# EmphaseMainBoard.net
KiCad netlist of a schematic drawn in Altium Designer
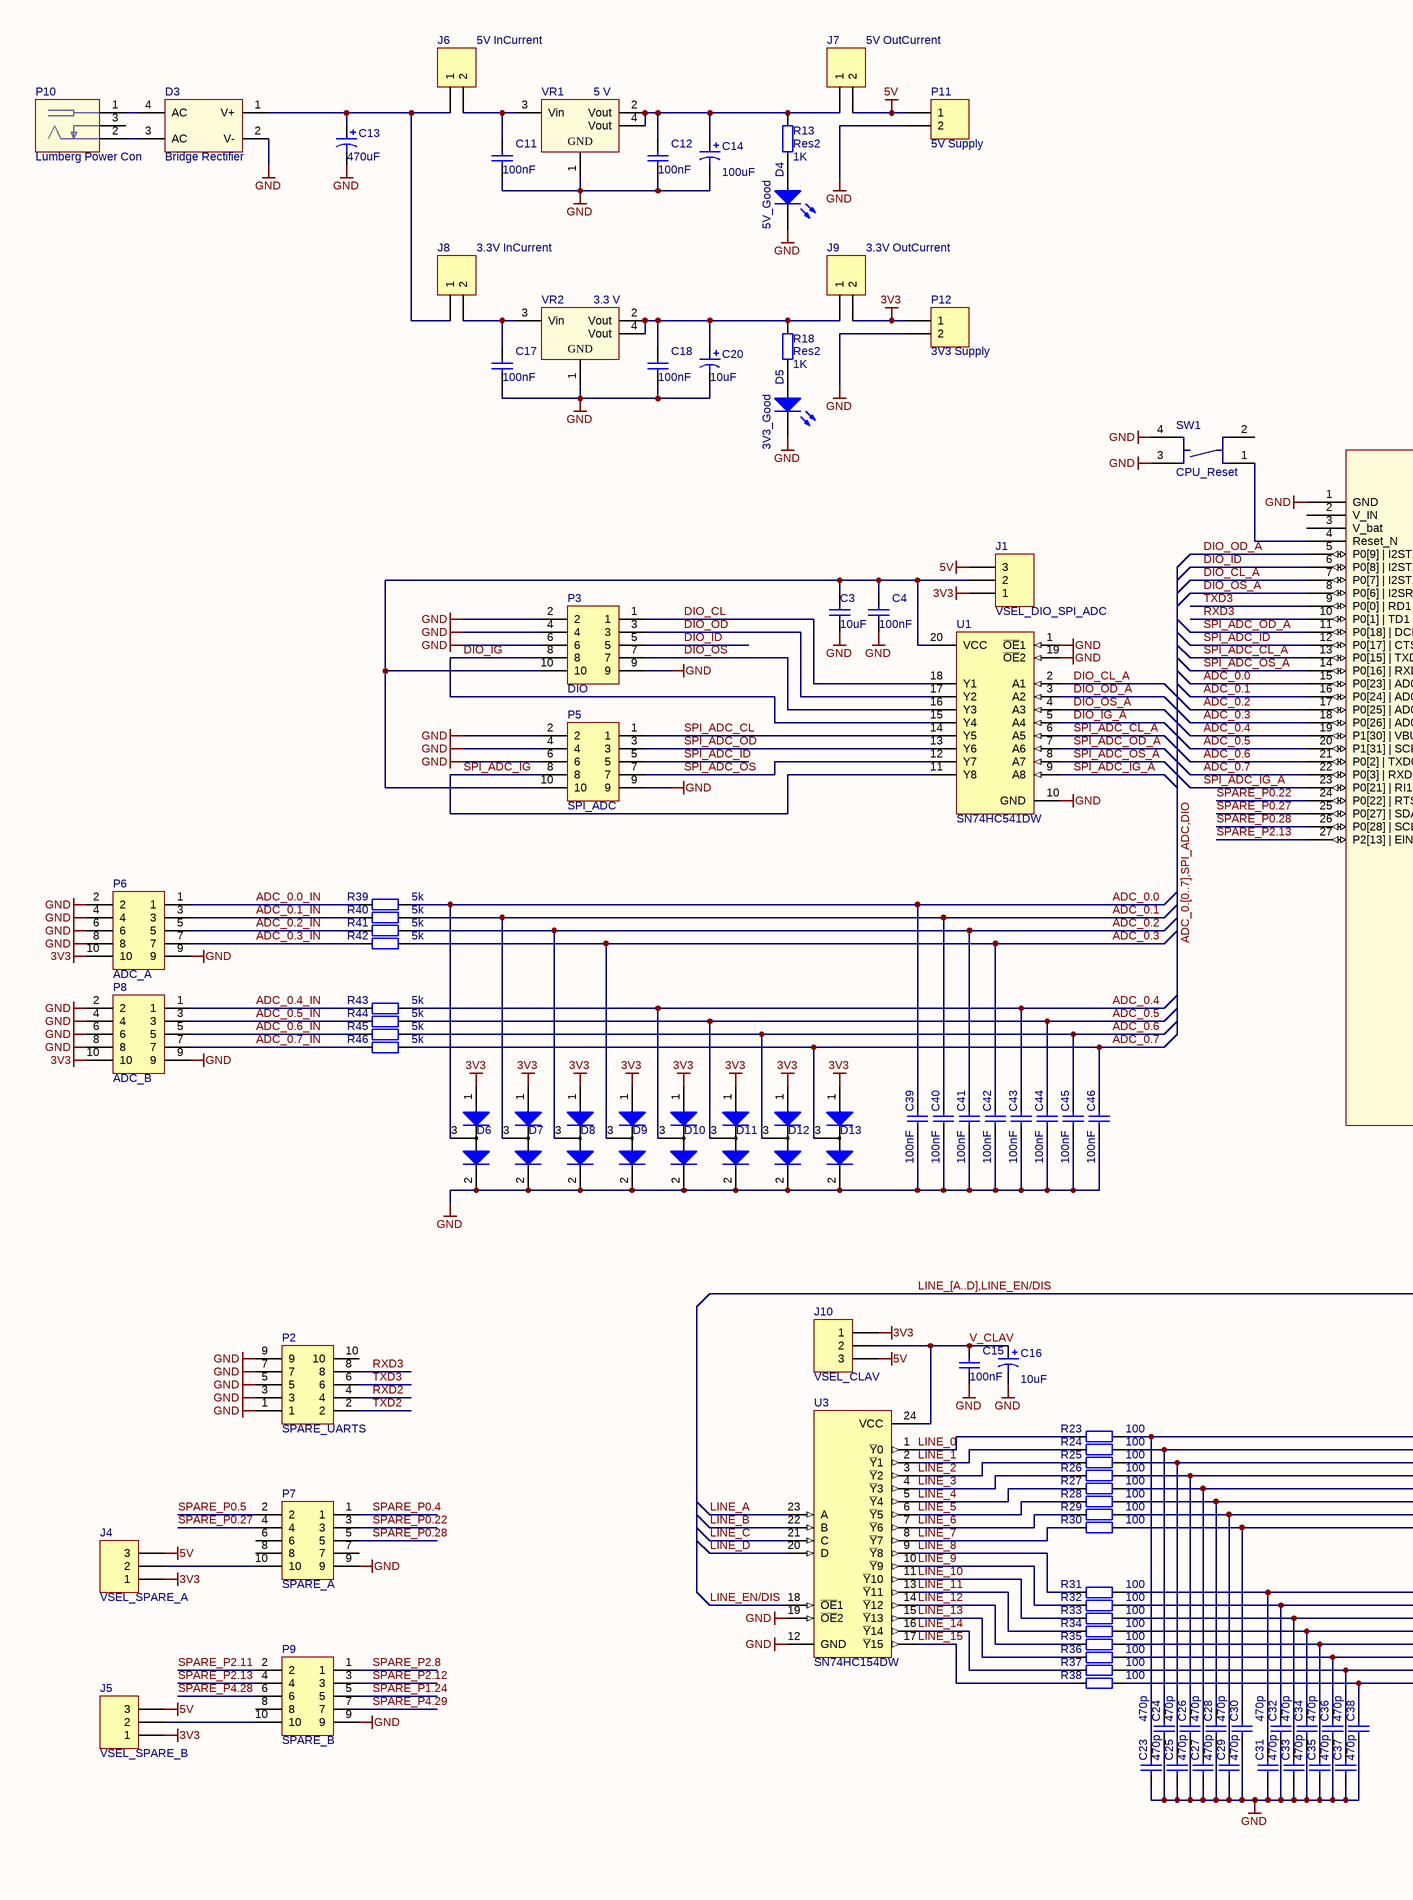
[diagram p0: EmphaseMainBoard.SchDoc, left]
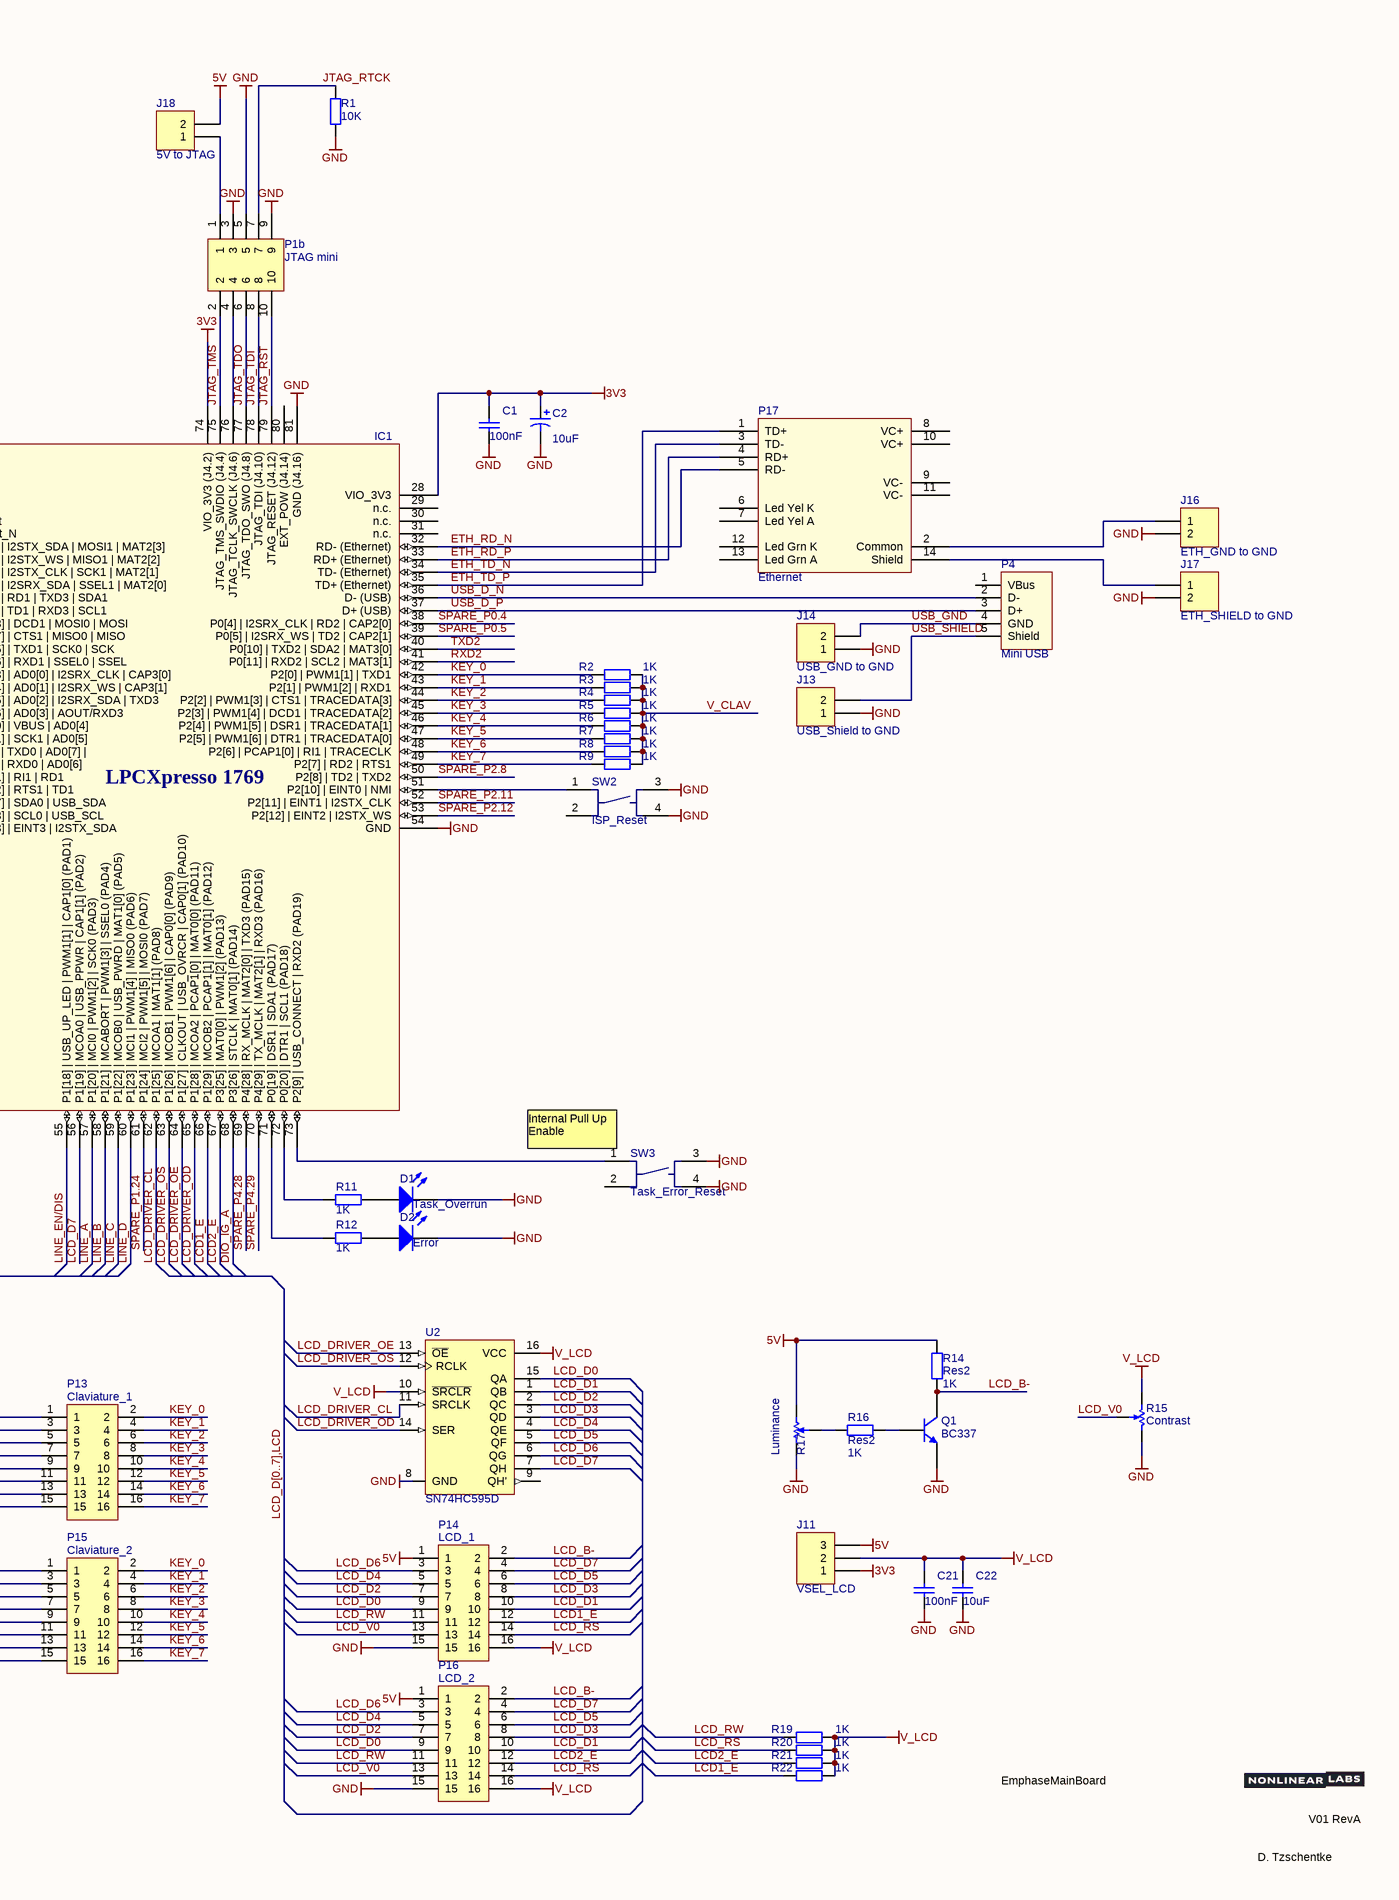
[diagram p1: EmphaseMainBoard.SchDoc, right]

(export (version "E")
  (design (tool "Eeschema 10.0.6"))
  (components
    (comp (ref "C1")
      (value "100nF")
      (footprint "6-0805_N")
      (description "Capacitor (Semiconductor SIM Model)")
      (fields (field (name "Comment") "Cap Semi") (field (name "PUBLISHER") "Altium Limited"))
      (libsource (lib "Miscellaneous Devices") (part "Cap Semi"))
    )
    (comp (ref "C2")
      (value "10uF")
      (footprint "6-0805_N")
      (description "Polarized Capacitor (Radial)")
      (fields (field (name "Comment") "Cap Pol1") (field (name "PUBLISHER") "Altium Limited"))
      (libsource (lib "Miscellaneous Devices") (part "Cap Pol1"))
    )
    (comp (ref "C3")
      (value "10uF")
      (footprint "6-0805_N")
      (description "Capacitor (Semiconductor SIM Model)")
      (fields (field (name "Comment") "Cap Semi") (field (name "PUBLISHER") "Altium Limited"))
      (libsource (lib "Miscellaneous Devices") (part "Cap Semi"))
    )
    (comp (ref "C4")
      (value "100nF")
      (footprint "6-0805_N")
      (description "Capacitor (Semiconductor SIM Model)")
      (fields (field (name "Comment") "Cap Semi") (field (name "PUBLISHER") "Altium Limited"))
      (libsource (lib "Miscellaneous Devices") (part "Cap Semi"))
    )
    (comp (ref "C11")
      (value "100nF")
      (footprint "6-0805_N")
      (description "Capacitor (Semiconductor SIM Model)")
      (fields (field (name "Comment") "Cap Semi") (field (name "PUBLISHER") "Altium Limited"))
      (libsource (lib "Miscellaneous Devices") (part "Cap Semi"))
    )
    (comp (ref "C12")
      (value "100nF")
      (footprint "6-0805_N")
      (description "Capacitor (Semiconductor SIM Model)")
      (fields (field (name "Comment") "Cap Semi") (field (name "PUBLISHER") "Altium Limited"))
      (libsource (lib "Miscellaneous Devices") (part "Cap Semi"))
    )
    (comp (ref "C13")
      (value "470uF")
      (footprint "CAPPR3.5-8x20")
      (description "Polarized Capacitor (Radial)")
      (fields (field (name "Comment") "Cap Pol1") (field (name "PUBLISHER") "Altium Limited"))
      (libsource (lib "Miscellaneous Devices") (part "Cap Pol1"))
    )
    (comp (ref "C14")
      (value "100uF")
      (footprint "CAPPR2.5-6.3x11")
      (description "Polarized Capacitor (Radial)")
      (fields (field (name "Comment") "Cap Pol1") (field (name "PUBLISHER") "Altium Limited"))
      (libsource (lib "Miscellaneous Devices") (part "Cap Pol1"))
    )
    (comp (ref "C15")
      (value "100nF")
      (footprint "6-0805_N")
      (description "Capacitor (Semiconductor SIM Model)")
      (fields (field (name "Comment") "Cap Semi") (field (name "PUBLISHER") "Altium Limited"))
      (libsource (lib "Miscellaneous Devices") (part "Cap Semi"))
    )
    (comp (ref "C16")
      (value "10uF")
      (footprint "6-0805_N")
      (description "Polarized Capacitor (Radial)")
      (fields (field (name "Comment") "Cap Pol1") (field (name "PUBLISHER") "Altium Limited"))
      (libsource (lib "Miscellaneous Devices") (part "Cap Pol1"))
    )
    (comp (ref "C17")
      (value "100nF")
      (footprint "6-0805_N")
      (description "Capacitor (Semiconductor SIM Model)")
      (fields (field (name "Comment") "Cap Semi") (field (name "PUBLISHER") "Altium Limited"))
      (libsource (lib "Miscellaneous Devices") (part "Cap Semi"))
    )
    (comp (ref "C18")
      (value "100nF")
      (footprint "6-0805_N")
      (description "Capacitor (Semiconductor SIM Model)")
      (fields (field (name "Comment") "Cap Semi") (field (name "PUBLISHER") "Altium Limited"))
      (libsource (lib "Miscellaneous Devices") (part "Cap Semi"))
    )
    (comp (ref "C20")
      (value "10uF")
      (footprint "CAPPR2.5-6.3x11")
      (description "Polarized Capacitor (Radial)")
      (fields (field (name "Comment") "Cap Pol1") (field (name "PUBLISHER") "Altium Limited"))
      (libsource (lib "Miscellaneous Devices") (part "Cap Pol1"))
    )
    (comp (ref "C21")
      (value "100nF")
      (footprint "6-0805_N")
      (description "Capacitor (Semiconductor SIM Model)")
      (fields (field (name "Comment") "Cap Semi") (field (name "PUBLISHER") "Altium Limited"))
      (libsource (lib "Miscellaneous Devices") (part "Cap Semi"))
    )
    (comp (ref "C22")
      (value "10uF")
      (footprint "6-0805_N")
      (description "Capacitor (Semiconductor SIM Model)")
      (fields (field (name "Comment") "Cap Semi") (field (name "PUBLISHER") "Altium Limited"))
      (libsource (lib "Miscellaneous Devices") (part "Cap Semi"))
    )
    (comp (ref "C23")
      (value "470p")
      (footprint "6-0805_N")
      (description "Capacitor (Semiconductor SIM Model)")
      (fields (field (name "Comment") "Cap Semi") (field (name "PUBLISHER") "Altium Limited"))
      (libsource (lib "Miscellaneous Devices") (part "Cap Semi"))
    )
    (comp (ref "C24")
      (value "470p")
      (footprint "6-0805_N")
      (description "Capacitor (Semiconductor SIM Model)")
      (fields (field (name "Comment") "Cap Semi") (field (name "PUBLISHER") "Altium Limited"))
      (libsource (lib "Miscellaneous Devices") (part "Cap Semi"))
    )
    (comp (ref "C25")
      (value "470p")
      (footprint "6-0805_N")
      (description "Capacitor (Semiconductor SIM Model)")
      (fields (field (name "Comment") "Cap Semi") (field (name "PUBLISHER") "Altium Limited"))
      (libsource (lib "Miscellaneous Devices") (part "Cap Semi"))
    )
    (comp (ref "C26")
      (value "470p")
      (footprint "6-0805_N")
      (description "Capacitor (Semiconductor SIM Model)")
      (fields (field (name "Comment") "Cap Semi") (field (name "PUBLISHER") "Altium Limited"))
      (libsource (lib "Miscellaneous Devices") (part "Cap Semi"))
    )
    (comp (ref "C27")
      (value "470p")
      (footprint "6-0805_N")
      (description "Capacitor (Semiconductor SIM Model)")
      (fields (field (name "Comment") "Cap Semi") (field (name "PUBLISHER") "Altium Limited"))
      (libsource (lib "Miscellaneous Devices") (part "Cap Semi"))
    )
    (comp (ref "C28")
      (value "470p")
      (footprint "6-0805_N")
      (description "Capacitor (Semiconductor SIM Model)")
      (fields (field (name "Comment") "Cap Semi") (field (name "PUBLISHER") "Altium Limited"))
      (libsource (lib "Miscellaneous Devices") (part "Cap Semi"))
    )
    (comp (ref "C29")
      (value "470p")
      (footprint "6-0805_N")
      (description "Capacitor (Semiconductor SIM Model)")
      (fields (field (name "Comment") "Cap Semi") (field (name "PUBLISHER") "Altium Limited"))
      (libsource (lib "Miscellaneous Devices") (part "Cap Semi"))
    )
    (comp (ref "C30")
      (value "470p")
      (footprint "6-0805_N")
      (description "Capacitor (Semiconductor SIM Model)")
      (fields (field (name "Comment") "Cap Semi") (field (name "PUBLISHER") "Altium Limited"))
      (libsource (lib "Miscellaneous Devices") (part "Cap Semi"))
    )
    (comp (ref "C31")
      (value "470p")
      (footprint "6-0805_N")
      (description "Capacitor (Semiconductor SIM Model)")
      (fields (field (name "Comment") "Cap Semi") (field (name "PUBLISHER") "Altium Limited"))
      (libsource (lib "Miscellaneous Devices") (part "Cap Semi"))
    )
    (comp (ref "C32")
      (value "470p")
      (footprint "6-0805_N")
      (description "Capacitor (Semiconductor SIM Model)")
      (fields (field (name "Comment") "Cap Semi") (field (name "PUBLISHER") "Altium Limited"))
      (libsource (lib "Miscellaneous Devices") (part "Cap Semi"))
    )
    (comp (ref "C33")
      (value "470p")
      (footprint "6-0805_N")
      (description "Capacitor (Semiconductor SIM Model)")
      (fields (field (name "Comment") "Cap Semi") (field (name "PUBLISHER") "Altium Limited"))
      (libsource (lib "Miscellaneous Devices") (part "Cap Semi"))
    )
    (comp (ref "C34")
      (value "470p")
      (footprint "6-0805_N")
      (description "Capacitor (Semiconductor SIM Model)")
      (fields (field (name "Comment") "Cap Semi") (field (name "PUBLISHER") "Altium Limited"))
      (libsource (lib "Miscellaneous Devices") (part "Cap Semi"))
    )
    (comp (ref "C35")
      (value "470p")
      (footprint "6-0805_N")
      (description "Capacitor (Semiconductor SIM Model)")
      (fields (field (name "Comment") "Cap Semi") (field (name "PUBLISHER") "Altium Limited"))
      (libsource (lib "Miscellaneous Devices") (part "Cap Semi"))
    )
    (comp (ref "C36")
      (value "470p")
      (footprint "6-0805_N")
      (description "Capacitor (Semiconductor SIM Model)")
      (fields (field (name "Comment") "Cap Semi") (field (name "PUBLISHER") "Altium Limited"))
      (libsource (lib "Miscellaneous Devices") (part "Cap Semi"))
    )
    (comp (ref "C37")
      (value "470p")
      (footprint "6-0805_N")
      (description "Capacitor (Semiconductor SIM Model)")
      (fields (field (name "Comment") "Cap Semi") (field (name "PUBLISHER") "Altium Limited"))
      (libsource (lib "Miscellaneous Devices") (part "Cap Semi"))
    )
    (comp (ref "C38")
      (value "470p")
      (footprint "6-0805_N")
      (description "Capacitor (Semiconductor SIM Model)")
      (fields (field (name "Comment") "Cap Semi") (field (name "PUBLISHER") "Altium Limited"))
      (libsource (lib "Miscellaneous Devices") (part "Cap Semi"))
    )
    (comp (ref "C39")
      (value "100nF")
      (footprint "6-0805_N")
      (description "Capacitor (Semiconductor SIM Model)")
      (fields (field (name "Comment") "Cap Semi") (field (name "PUBLISHER") "Altium Limited"))
      (libsource (lib "Miscellaneous Devices") (part "Cap Semi"))
    )
    (comp (ref "C40")
      (value "100nF")
      (footprint "6-0805_N")
      (description "Capacitor (Semiconductor SIM Model)")
      (fields (field (name "Comment") "Cap Semi") (field (name "PUBLISHER") "Altium Limited"))
      (libsource (lib "Miscellaneous Devices") (part "Cap Semi"))
    )
    (comp (ref "C41")
      (value "100nF")
      (footprint "6-0805_N")
      (description "Capacitor (Semiconductor SIM Model)")
      (fields (field (name "Comment") "Cap Semi") (field (name "PUBLISHER") "Altium Limited"))
      (libsource (lib "Miscellaneous Devices") (part "Cap Semi"))
    )
    (comp (ref "C42")
      (value "100nF")
      (footprint "6-0805_N")
      (description "Capacitor (Semiconductor SIM Model)")
      (fields (field (name "Comment") "Cap Semi") (field (name "PUBLISHER") "Altium Limited"))
      (libsource (lib "Miscellaneous Devices") (part "Cap Semi"))
    )
    (comp (ref "C43")
      (value "100nF")
      (footprint "6-0805_N")
      (description "Capacitor (Semiconductor SIM Model)")
      (fields (field (name "Comment") "Cap Semi") (field (name "PUBLISHER") "Altium Limited"))
      (libsource (lib "Miscellaneous Devices") (part "Cap Semi"))
    )
    (comp (ref "C44")
      (value "100nF")
      (footprint "6-0805_N")
      (description "Capacitor (Semiconductor SIM Model)")
      (fields (field (name "Comment") "Cap Semi") (field (name "PUBLISHER") "Altium Limited"))
      (libsource (lib "Miscellaneous Devices") (part "Cap Semi"))
    )
    (comp (ref "C45")
      (value "100nF")
      (footprint "6-0805_N")
      (description "Capacitor (Semiconductor SIM Model)")
      (fields (field (name "Comment") "Cap Semi") (field (name "PUBLISHER") "Altium Limited"))
      (libsource (lib "Miscellaneous Devices") (part "Cap Semi"))
    )
    (comp (ref "C46")
      (value "100nF")
      (footprint "6-0805_N")
      (description "Capacitor (Semiconductor SIM Model)")
      (fields (field (name "Comment") "Cap Semi") (field (name "PUBLISHER") "Altium Limited"))
      (libsource (lib "Miscellaneous Devices") (part "Cap Semi"))
    )
    (comp (ref "D1")
      (value "Task_Overrun")
      (footprint "6-0805_M")
      (description "Typical BLUE SiC LED")
      (fields (field (name "PUBLISHER") "Altium Limited"))
      (libsource (lib "Miscellaneous Devices") (part "LED3"))
    )
    (comp (ref "D2")
      (value "Error")
      (footprint "6-0805_M")
      (description "Typical BLUE SiC LED")
      (fields (field (name "PUBLISHER") "Altium Limited"))
      (libsource (lib "Miscellaneous Devices") (part "LED3"))
    )
    (comp (ref "D3")
      (value "Bridge Rectifier")
      (footprint "SDIP")
      (fields (field (name "PUBLISHER") "NONLINEAR LABS"))
      (libsource (lib "BridgeRectifier") (part "Bridge Rectifiers"))
    )
    (comp (ref "D4")
      (value "5V_Good")
      (footprint "6-0805_M")
      (description "Typical BLUE SiC LED")
      (fields (field (name "PUBLISHER") "Altium Limited"))
      (libsource (lib "Miscellaneous Devices") (part "LED3"))
    )
    (comp (ref "D5")
      (value "3V3_Good")
      (footprint "6-0805_M")
      (description "Typical BLUE SiC LED")
      (fields (field (name "PUBLISHER") "Altium Limited"))
      (libsource (lib "Miscellaneous Devices") (part "LED3"))
    )
    (comp (ref "D6")
      (value "Double Diode")
      (footprint "SOT23-3N")
      (description "High Speed Double Diode")
      (fields (field (name "PUBLISHER") "NONLINEAR LABS"))
      (libsource (lib "DoubleDiode") (part "Double Diode"))
    )
    (comp (ref "D7")
      (value "Double Diode")
      (footprint "SOT23-3N")
      (description "High Speed Double Diode")
      (fields (field (name "PUBLISHER") "NONLINEAR LABS"))
      (libsource (lib "DoubleDiode") (part "Double Diode"))
    )
    (comp (ref "D8")
      (value "Double Diode")
      (footprint "SOT23-3N")
      (description "High Speed Double Diode")
      (fields (field (name "PUBLISHER") "NONLINEAR LABS"))
      (libsource (lib "DoubleDiode") (part "Double Diode"))
    )
    (comp (ref "D9")
      (value "Double Diode")
      (footprint "SOT23-3N")
      (description "High Speed Double Diode")
      (fields (field (name "PUBLISHER") "NONLINEAR LABS"))
      (libsource (lib "DoubleDiode") (part "Double Diode"))
    )
    (comp (ref "D10")
      (value "Double Diode")
      (footprint "SOT23-3N")
      (description "High Speed Double Diode")
      (fields (field (name "PUBLISHER") "NONLINEAR LABS"))
      (libsource (lib "DoubleDiode") (part "Double Diode"))
    )
    (comp (ref "D11")
      (value "Double Diode")
      (footprint "SOT23-3N")
      (description "High Speed Double Diode")
      (fields (field (name "PUBLISHER") "NONLINEAR LABS"))
      (libsource (lib "DoubleDiode") (part "Double Diode"))
    )
    (comp (ref "D12")
      (value "Double Diode")
      (footprint "SOT23-3N")
      (description "High Speed Double Diode")
      (fields (field (name "PUBLISHER") "NONLINEAR LABS"))
      (libsource (lib "DoubleDiode") (part "Double Diode"))
    )
    (comp (ref "D13")
      (value "Double Diode")
      (footprint "SOT23-3N")
      (description "High Speed Double Diode")
      (fields (field (name "PUBLISHER") "NONLINEAR LABS"))
      (libsource (lib "DoubleDiode") (part "Double Diode"))
    )
    (comp (ref "IC1")
      (value "~")
      (footprint "LPCXpresso1769")
      (description "Capacitor (Semiconductor SIM Model)")
      (libsource (lib "LPCXpresso1769") (part "Component_1"))
    )
    (comp (ref "J1")
      (value "VSEL_DIO_SPI_ADC")
      (footprint "HDR1X3")
      (description "Header, 3-Pin")
      (fields (field (name "PUBLISHER") "Altium Limited"))
      (libsource (lib "") (part "Header 3_1"))
    )
    (comp (ref "J4")
      (value "VSEL_SPARE_A")
      (footprint "HDR1X3")
      (description "Header, 3-Pin")
      (fields (field (name "PUBLISHER") "Altium Limited"))
      (libsource (lib "Miscellaneous Connectors") (part "Header 3"))
    )
    (comp (ref "J5")
      (value "VSEL_SPARE_B")
      (footprint "HDR1X3")
      (description "Header, 3-Pin")
      (fields (field (name "PUBLISHER") "Altium Limited"))
      (libsource (lib "Miscellaneous Connectors") (part "Header 3"))
    )
    (comp (ref "J6")
      (value "5V InCurrent")
      (footprint "HDR1X2")
      (description "Header, 2-Pin")
      (fields (field (name "PUBLISHER") "Altium Limited"))
      (libsource (lib "") (part "Header 2_2"))
    )
    (comp (ref "J7")
      (value "5V OutCurrent")
      (footprint "HDR1X2")
      (description "Header, 2-Pin")
      (fields (field (name "PUBLISHER") "Altium Limited"))
      (libsource (lib "") (part "Header 2_2"))
    )
    (comp (ref "J8")
      (value "3.3V InCurrent")
      (footprint "HDR1X2")
      (description "Header, 2-Pin")
      (fields (field (name "PUBLISHER") "Altium Limited"))
      (libsource (lib "") (part "Header 2_2"))
    )
    (comp (ref "J9")
      (value "3.3V OutCurrent")
      (footprint "HDR1X2")
      (description "Header, 2-Pin")
      (fields (field (name "PUBLISHER") "Altium Limited"))
      (libsource (lib "") (part "Header 2_2"))
    )
    (comp (ref "J10")
      (value "VSEL_CLAV")
      (footprint "HDR1X3")
      (description "Header, 3-Pin")
      (fields (field (name "PUBLISHER") "Altium Limited"))
      (libsource (lib "") (part "Header 3_2"))
    )
    (comp (ref "J11")
      (value "VSEL_LCD")
      (footprint "HDR1X3")
      (description "Header, 3-Pin")
      (fields (field (name "PUBLISHER") "Altium Limited"))
      (libsource (lib "Miscellaneous Connectors") (part "Header 3"))
    )
    (comp (ref "J13")
      (value "USB_Shield to GND")
      (footprint "HDR1X2")
      (description "Header, 2-Pin")
      (fields (field (name "PUBLISHER") "Altium Limited"))
      (libsource (lib "Miscellaneous Connectors") (part "Header 2"))
    )
    (comp (ref "J14")
      (value "USB_GND to GND")
      (footprint "HDR1X2")
      (description "Header, 2-Pin")
      (fields (field (name "PUBLISHER") "Altium Limited"))
      (libsource (lib "Miscellaneous Connectors") (part "Header 2"))
    )
    (comp (ref "J16")
      (value "ETH_GND to GND")
      (footprint "HDR1X2")
      (description "Header, 2-Pin")
      (fields (field (name "PUBLISHER") "Altium Limited"))
      (libsource (lib "") (part "Header 2_1"))
    )
    (comp (ref "J17")
      (value "ETH_SHIELD to GND")
      (footprint "HDR1X2")
      (description "Header, 2-Pin")
      (fields (field (name "PUBLISHER") "Altium Limited"))
      (libsource (lib "") (part "Header 2_1"))
    )
    (comp (ref "J18")
      (value "5V to JTAG")
      (footprint "HDR1X2")
      (description "Header, 2-Pin")
      (fields (field (name "PUBLISHER") "Altium Limited"))
      (libsource (lib "Miscellaneous Connectors") (part "Header 2"))
    )
    (comp (ref "P1b")
      (value "JTAG mini")
      (footprint "10 pol Header SMD")
      (description "JTAG")
      (fields (field (name "PUBLISHER") "NONLINEAR LABS"))
      (libsource (lib "") (part "10 pol Header_2"))
    )
    (comp (ref "P2")
      (value "SPARE_UARTS")
      (footprint "10 pol Header")
      (description "10 pol Header")
      (fields (field (name "PUBLISHER") "NONLINEAR LABS"))
      (libsource (lib "") (part "10 pol Header_1"))
    )
    (comp (ref "P3")
      (value "DIO")
      (footprint "10 pol Header")
      (description "10 pol Header")
      (fields (field (name "PUBLISHER") "NONLINEAR LABS"))
      (libsource (lib "10polHeader") (part "10 pol Header"))
    )
    (comp (ref "P4")
      (value "Mini USB")
      (footprint "Mini USB Socket - Typ B")
      (fields (field (name "PUBLISHER") "NONLINEAR LABS"))
      (libsource (lib "MiniUsb") (part "Mini USB Jack B"))
    )
    (comp (ref "P5")
      (value "SPI_ADC")
      (footprint "10 pol Header")
      (description "10 pol Header")
      (fields (field (name "PUBLISHER") "NONLINEAR LABS"))
      (libsource (lib "10polHeader") (part "10 pol Header"))
    )
    (comp (ref "P6")
      (value "ADC_A")
      (footprint "10 pol Header")
      (description "10 pol Header")
      (fields (field (name "PUBLISHER") "NONLINEAR LABS"))
      (libsource (lib "10polHeader") (part "10 pol Header"))
    )
    (comp (ref "P7")
      (value "SPARE_A")
      (footprint "10 pol Header")
      (description "10 pol Header")
      (fields (field (name "PUBLISHER") "NONLINEAR LABS"))
      (libsource (lib "10polHeader") (part "10 pol Header"))
    )
    (comp (ref "P8")
      (value "ADC_B")
      (footprint "10 pol Header")
      (description "10 pol Header")
      (fields (field (name "PUBLISHER") "NONLINEAR LABS"))
      (libsource (lib "10polHeader") (part "10 pol Header"))
    )
    (comp (ref "P9")
      (value "SPARE_B")
      (footprint "10 pol Header")
      (description "10 pol Header")
      (fields (field (name "PUBLISHER") "NONLINEAR LABS"))
      (libsource (lib "10polHeader") (part "10 pol Header"))
    )
    (comp (ref "P10")
      (value "Lumberg Power Con")
      (footprint "LumbergPowerCon")
      (description "Lumberg Power Connector")
      (fields (field (name "PUBLISHER") "NONLINEAR LABS"))
      (libsource (lib "LumbergPowerCon") (part "Lumberg Power Connector"))
    )
    (comp (ref "P11")
      (value "5V Supply")
      (footprint "HDR1X2")
      (description "Header, 2-Pin")
      (fields (field (name "PUBLISHER") "Altium Limited"))
      (libsource (lib "") (part "Header 2_1"))
    )
    (comp (ref "P12")
      (value "3V3 Supply")
      (footprint "HDR1X2")
      (description "Header, 2-Pin")
      (fields (field (name "PUBLISHER") "Altium Limited"))
      (libsource (lib "") (part "Header 2_1"))
    )
    (comp (ref "P13")
      (value "Claviature_1")
      (footprint "16 pol Header")
      (description "16 pol Header")
      (fields (field (name "PUBLISHER") "NONLINEAR LABS"))
      (libsource (lib "16polHeader") (part "16 pol Header"))
    )
    (comp (ref "P14")
      (value "LCD_1")
      (footprint "16 pol Header")
      (description "16 pol Header")
      (fields (field (name "PUBLISHER") "NONLINEAR LABS"))
      (libsource (lib "16polHeader") (part "16 pol Header"))
    )
    (comp (ref "P15")
      (value "Claviature_2")
      (footprint "16 pol Header")
      (description "16 pol Header")
      (fields (field (name "PUBLISHER") "NONLINEAR LABS"))
      (libsource (lib "16polHeader") (part "16 pol Header"))
    )
    (comp (ref "P16")
      (value "LCD_2")
      (footprint "16 pol Header")
      (description "16 pol Header")
      (fields (field (name "PUBLISHER") "NONLINEAR LABS"))
      (libsource (lib "16polHeader") (part "16 pol Header"))
    )
    (comp (ref "P17")
      (value "Ethernet")
      (footprint "Ethernet RJ-45")
      (description "Bel Stewart - MagJack 10/100 RJ-45 Ethernet")
      (fields (field (name "PUBLISHER") "NONLINEAR LABS"))
      (libsource (lib "BelEthernet") (part "Ethernet Jack"))
    )
    (comp (ref "Q1")
      (value "BC337")
      (footprint "TO-226-AA")
      (description "NPN Bipolar Transistor")
      (fields (field (name "PUBLISHER") "Altium Limited"))
      (libsource (lib "Miscellaneous Devices") (part "NPN"))
    )
    (comp (ref "R1")
      (value "10K")
      (footprint "6-0805")
      (description "Resistor")
      (fields (field (name "Comment") "Res2") (field (name "PUBLISHER") "Altium Limited"))
      (libsource (lib "Miscellaneous Devices") (part "Res2"))
    )
    (comp (ref "R2")
      (value "1K")
      (footprint "6-0805")
      (description "Resistor")
      (fields (field (name "Comment") "Res2") (field (name "PUBLISHER") "Altium Limited"))
      (libsource (lib "Miscellaneous Devices") (part "Res2"))
    )
    (comp (ref "R3")
      (value "1K")
      (footprint "6-0805")
      (description "Resistor")
      (fields (field (name "Comment") "Res2") (field (name "PUBLISHER") "Altium Limited"))
      (libsource (lib "Miscellaneous Devices") (part "Res2"))
    )
    (comp (ref "R4")
      (value "1K")
      (footprint "6-0805")
      (description "Resistor")
      (fields (field (name "Comment") "Res2") (field (name "PUBLISHER") "Altium Limited"))
      (libsource (lib "Miscellaneous Devices") (part "Res2"))
    )
    (comp (ref "R5")
      (value "1K")
      (footprint "6-0805")
      (description "Resistor")
      (fields (field (name "Comment") "Res2") (field (name "PUBLISHER") "Altium Limited"))
      (libsource (lib "Miscellaneous Devices") (part "Res2"))
    )
    (comp (ref "R6")
      (value "1K")
      (footprint "6-0805")
      (description "Resistor")
      (fields (field (name "Comment") "Res2") (field (name "PUBLISHER") "Altium Limited"))
      (libsource (lib "Miscellaneous Devices") (part "Res2"))
    )
    (comp (ref "R7")
      (value "1K")
      (footprint "6-0805")
      (description "Resistor")
      (fields (field (name "Comment") "Res2") (field (name "PUBLISHER") "Altium Limited"))
      (libsource (lib "Miscellaneous Devices") (part "Res2"))
    )
    (comp (ref "R8")
      (value "1K")
      (footprint "6-0805")
      (description "Resistor")
      (fields (field (name "Comment") "Res2") (field (name "PUBLISHER") "Altium Limited"))
      (libsource (lib "Miscellaneous Devices") (part "Res2"))
    )
    (comp (ref "R9")
      (value "1K")
      (footprint "6-0805")
      (description "Resistor")
      (fields (field (name "Comment") "Res2") (field (name "PUBLISHER") "Altium Limited"))
      (libsource (lib "Miscellaneous Devices") (part "Res2"))
    )
    (comp (ref "R11")
      (value "1K")
      (footprint "6-0805")
      (description "Resistor")
      (fields (field (name "Comment") "Res2") (field (name "PUBLISHER") "Altium Limited"))
      (libsource (lib "Miscellaneous Devices") (part "Res2"))
    )
    (comp (ref "R12")
      (value "1K")
      (footprint "6-0805")
      (description "Resistor")
      (fields (field (name "Comment") "Res2") (field (name "PUBLISHER") "Altium Limited"))
      (libsource (lib "Miscellaneous Devices") (part "Res2"))
    )
    (comp (ref "R13")
      (value "Res2")
      (footprint "6-0805")
      (description "Resistor")
      (fields (field (name "ALTIUM_VALUE") "1K") (field (name "PUBLISHER") "Altium Limited"))
      (libsource (lib "") (part "Res2_1"))
    )
    (comp (ref "R14")
      (value "Res2")
      (footprint "6-0805")
      (description "Resistor")
      (fields (field (name "ALTIUM_VALUE") "1K") (field (name "PUBLISHER") "Altium Limited"))
      (libsource (lib "") (part "Res2_1"))
    )
    (comp (ref "R15")
      (value "Contrast")
      (footprint "MiniPot")
      (description "Square Trimming Potentiometer")
      (fields (field (name "PUBLISHER") "Altium Limited"))
      (libsource (lib "Miscellaneous Devices") (part "RPot SM"))
    )
    (comp (ref "R16")
      (value "Res2")
      (footprint "6-0805")
      (description "Resistor")
      (fields (field (name "ALTIUM_VALUE") "1K") (field (name "PUBLISHER") "Altium Limited"))
      (libsource (lib "") (part "Res2_2"))
    )
    (comp (ref "R17")
      (value "Luminance")
      (footprint "MiniPot")
      (description "Square Trimming Potentiometer")
      (fields (field (name "PUBLISHER") "Altium Limited"))
      (libsource (lib "Miscellaneous Devices") (part "RPot SM"))
    )
    (comp (ref "R18")
      (value "Res2")
      (footprint "6-0805")
      (description "Resistor")
      (fields (field (name "ALTIUM_VALUE") "1K") (field (name "PUBLISHER") "Altium Limited"))
      (libsource (lib "") (part "Res2_1"))
    )
    (comp (ref "R19")
      (value "1K")
      (footprint "6-0805")
      (description "Resistor")
      (fields (field (name "Comment") "Res2") (field (name "PUBLISHER") "Altium Limited"))
      (libsource (lib "Miscellaneous Devices") (part "Res2"))
    )
    (comp (ref "R20")
      (value "1K")
      (footprint "6-0805")
      (description "Resistor")
      (fields (field (name "Comment") "Res2") (field (name "PUBLISHER") "Altium Limited"))
      (libsource (lib "Miscellaneous Devices") (part "Res2"))
    )
    (comp (ref "R21")
      (value "1K")
      (footprint "6-0805")
      (description "Resistor")
      (fields (field (name "Comment") "Res2") (field (name "PUBLISHER") "Altium Limited"))
      (libsource (lib "Miscellaneous Devices") (part "Res2"))
    )
    (comp (ref "R22")
      (value "1K")
      (footprint "6-0805")
      (description "Resistor")
      (fields (field (name "Comment") "Res2") (field (name "PUBLISHER") "Altium Limited"))
      (libsource (lib "Miscellaneous Devices") (part "Res2"))
    )
    (comp (ref "R23")
      (value "100")
      (footprint "6-0805")
      (description "Resistor")
      (fields (field (name "Comment") "Res2") (field (name "PUBLISHER") "Altium Limited"))
      (libsource (lib "Miscellaneous Devices") (part "Res2"))
    )
    (comp (ref "R24")
      (value "100")
      (footprint "6-0805")
      (description "Resistor")
      (fields (field (name "Comment") "Res2") (field (name "PUBLISHER") "Altium Limited"))
      (libsource (lib "Miscellaneous Devices") (part "Res2"))
    )
    (comp (ref "R25")
      (value "100")
      (footprint "6-0805")
      (description "Resistor")
      (fields (field (name "Comment") "Res2") (field (name "PUBLISHER") "Altium Limited"))
      (libsource (lib "Miscellaneous Devices") (part "Res2"))
    )
    (comp (ref "R26")
      (value "100")
      (footprint "6-0805")
      (description "Resistor")
      (fields (field (name "Comment") "Res2") (field (name "PUBLISHER") "Altium Limited"))
      (libsource (lib "Miscellaneous Devices") (part "Res2"))
    )
    (comp (ref "R27")
      (value "100")
      (footprint "6-0805")
      (description "Resistor")
      (fields (field (name "Comment") "Res2") (field (name "PUBLISHER") "Altium Limited"))
      (libsource (lib "Miscellaneous Devices") (part "Res2"))
    )
    (comp (ref "R28")
      (value "100")
      (footprint "6-0805")
      (description "Resistor")
      (fields (field (name "Comment") "Res2") (field (name "PUBLISHER") "Altium Limited"))
      (libsource (lib "Miscellaneous Devices") (part "Res2"))
    )
    (comp (ref "R29")
      (value "100")
      (footprint "6-0805")
      (description "Resistor")
      (fields (field (name "Comment") "Res2") (field (name "PUBLISHER") "Altium Limited"))
      (libsource (lib "Miscellaneous Devices") (part "Res2"))
    )
    (comp (ref "R30")
      (value "100")
      (footprint "6-0805")
      (description "Resistor")
      (fields (field (name "Comment") "Res2") (field (name "PUBLISHER") "Altium Limited"))
      (libsource (lib "Miscellaneous Devices") (part "Res2"))
    )
    (comp (ref "R31")
      (value "100")
      (footprint "6-0805")
      (description "Resistor")
      (fields (field (name "Comment") "Res2") (field (name "PUBLISHER") "Altium Limited"))
      (libsource (lib "Miscellaneous Devices") (part "Res2"))
    )
    (comp (ref "R32")
      (value "100")
      (footprint "6-0805")
      (description "Resistor")
      (fields (field (name "Comment") "Res2") (field (name "PUBLISHER") "Altium Limited"))
      (libsource (lib "Miscellaneous Devices") (part "Res2"))
    )
    (comp (ref "R33")
      (value "100")
      (footprint "6-0805")
      (description "Resistor")
      (fields (field (name "Comment") "Res2") (field (name "PUBLISHER") "Altium Limited"))
      (libsource (lib "Miscellaneous Devices") (part "Res2"))
    )
    (comp (ref "R34")
      (value "100")
      (footprint "6-0805")
      (description "Resistor")
      (fields (field (name "Comment") "Res2") (field (name "PUBLISHER") "Altium Limited"))
      (libsource (lib "Miscellaneous Devices") (part "Res2"))
    )
    (comp (ref "R35")
      (value "100")
      (footprint "6-0805")
      (description "Resistor")
      (fields (field (name "Comment") "Res2") (field (name "PUBLISHER") "Altium Limited"))
      (libsource (lib "Miscellaneous Devices") (part "Res2"))
    )
    (comp (ref "R36")
      (value "100")
      (footprint "6-0805")
      (description "Resistor")
      (fields (field (name "Comment") "Res2") (field (name "PUBLISHER") "Altium Limited"))
      (libsource (lib "Miscellaneous Devices") (part "Res2"))
    )
    (comp (ref "R37")
      (value "100")
      (footprint "6-0805")
      (description "Resistor")
      (fields (field (name "Comment") "Res2") (field (name "PUBLISHER") "Altium Limited"))
      (libsource (lib "Miscellaneous Devices") (part "Res2"))
    )
    (comp (ref "R38")
      (value "100")
      (footprint "6-0805")
      (description "Resistor")
      (fields (field (name "Comment") "Res2") (field (name "PUBLISHER") "Altium Limited"))
      (libsource (lib "Miscellaneous Devices") (part "Res2"))
    )
    (comp (ref "R39")
      (value "5k")
      (footprint "6-0805")
      (description "Resistor")
      (fields (field (name "Comment") "Res2") (field (name "PUBLISHER") "Altium Limited"))
      (libsource (lib "Miscellaneous Devices") (part "Res2"))
    )
    (comp (ref "R40")
      (value "5k")
      (footprint "6-0805")
      (description "Resistor")
      (fields (field (name "Comment") "Res2") (field (name "PUBLISHER") "Altium Limited"))
      (libsource (lib "Miscellaneous Devices") (part "Res2"))
    )
    (comp (ref "R41")
      (value "5k")
      (footprint "6-0805")
      (description "Resistor")
      (fields (field (name "Comment") "Res2") (field (name "PUBLISHER") "Altium Limited"))
      (libsource (lib "Miscellaneous Devices") (part "Res2"))
    )
    (comp (ref "R42")
      (value "5k")
      (footprint "6-0805")
      (description "Resistor")
      (fields (field (name "Comment") "Res2") (field (name "PUBLISHER") "Altium Limited"))
      (libsource (lib "Miscellaneous Devices") (part "Res2"))
    )
    (comp (ref "R43")
      (value "5k")
      (footprint "6-0805")
      (description "Resistor")
      (fields (field (name "Comment") "Res2") (field (name "PUBLISHER") "Altium Limited"))
      (libsource (lib "Miscellaneous Devices") (part "Res2"))
    )
    (comp (ref "R44")
      (value "5k")
      (footprint "6-0805")
      (description "Resistor")
      (fields (field (name "Comment") "Res2") (field (name "PUBLISHER") "Altium Limited"))
      (libsource (lib "Miscellaneous Devices") (part "Res2"))
    )
    (comp (ref "R45")
      (value "5k")
      (footprint "6-0805")
      (description "Resistor")
      (fields (field (name "Comment") "Res2") (field (name "PUBLISHER") "Altium Limited"))
      (libsource (lib "Miscellaneous Devices") (part "Res2"))
    )
    (comp (ref "R46")
      (value "5k")
      (footprint "6-0805")
      (description "Resistor")
      (fields (field (name "Comment") "Res2") (field (name "PUBLISHER") "Altium Limited"))
      (libsource (lib "Miscellaneous Devices") (part "Res2"))
    )
    (comp (ref "SW1")
      (value "CPU_Reset")
      (footprint "SMD Switch")
      (fields (field (name "PUBLISHER") "NONLINEAR LABS"))
      (libsource (lib "GenericSmdSwitch") (part "Generic SMD Switch"))
    )
    (comp (ref "SW2")
      (value "ISP_Reset")
      (footprint "SMD Switch")
      (fields (field (name "PUBLISHER") "NONLINEAR LABS"))
      (libsource (lib "GenericSmdSwitch") (part "Generic SMD Switch"))
    )
    (comp (ref "SW3")
      (value "Task_Error_Reset")
      (footprint "SMD Switch")
      (fields (field (name "PUBLISHER") "NONLINEAR LABS"))
      (libsource (lib "GenericSmdSwitch") (part "Generic SMD Switch"))
    )
    (comp (ref "U1")
      (value "SN74HC541DW")
      (footprint "DW020_N")
      (description "Octal Buffer/Driver with 3-State Outputs")
      (fields (field (name "PUBLISHER") "Altium Limited"))
      (libsource (lib "TI Logic Buffer Line Driver") (part "SN74HC541DW"))
    )
    (comp (ref "U2")
      (value "SN74HC595D")
      (footprint "D016_M")
      (description "8-Bit Shift Register with 3-State Output Registers")
      (fields (field (name "PUBLISHER") "Altium Limited"))
      (libsource (lib "TI Logic Register") (part "SN74HC595D"))
    )
    (comp (ref "U3")
      (value "SN74HC154DW")
      (footprint "SOIC127P1199-24AN")
      (description "4-Line to 16-Line Decoder / Demultiplexer")
      (fields (field (name "PUBLISHER") "Altium Limited"))
      (libsource (lib "TI Logic Decoder Demux") (part "SN74HC154DW"))
    )
    (comp (ref "VR1")
      (value "5 V")
      (footprint "SOT223-4N")
      (fields (field (name "PUBLISHER") "NONLINEAR LABS"))
      (libsource (lib "NX1117 VoltageRegulator") (part "Voltage Regulator"))
    )
    (comp (ref "VR2")
      (value "3.3 V")
      (footprint "SOT223-4N")
      (fields (field (name "PUBLISHER") "NONLINEAR LABS"))
      (libsource (lib "NX1117 VoltageRegulator") (part "Voltage Regulator"))
    )
  )
  (nets
    (net (code "4") (name "/ADC_0.0") (class "Default")
      (node (ref "C39") (pin "2") (pinfunction "2_2") (pintype "passive"))
      (node (ref "D6") (pin "3") (pintype "passive"))
      (node (ref "IC1") (pin "15") (pinfunction "P0[23]__AD0[0]__I2SRX_CLK__CAP3[0]_15") (pintype "bidirectional"))
      (node (ref "R39") (pin "1") (pinfunction "1_1") (pintype "passive"))
    )
    (net (code "5") (name "/ADC_0.0_IN") (class "Default")
      (node (ref "P6") (pin "1") (pinfunction "1_1") (pintype "passive"))
      (node (ref "R39") (pin "2") (pinfunction "2_2") (pintype "passive"))
    )
    (net (code "6") (name "/ADC_0.1") (class "Default")
      (node (ref "C40") (pin "2") (pinfunction "2_2") (pintype "passive"))
      (node (ref "D7") (pin "3") (pintype "passive"))
      (node (ref "IC1") (pin "16") (pinfunction "P0[24]__AD0[1]__I2SRX_WS__CAP3[1]_16") (pintype "bidirectional"))
      (node (ref "R40") (pin "1") (pinfunction "1_1") (pintype "passive"))
    )
    (net (code "7") (name "/ADC_0.1_IN") (class "Default")
      (node (ref "P6") (pin "3") (pinfunction "3_3") (pintype "passive"))
      (node (ref "R40") (pin "2") (pinfunction "2_2") (pintype "passive"))
    )
    (net (code "8") (name "/ADC_0.2") (class "Default")
      (node (ref "C41") (pin "2") (pinfunction "2_2") (pintype "passive"))
      (node (ref "D8") (pin "3") (pintype "passive"))
      (node (ref "IC1") (pin "17") (pinfunction "P0[25]__AD0[2]__I2SRX_SDA__TXD3_17") (pintype "bidirectional"))
      (node (ref "R41") (pin "1") (pinfunction "1_1") (pintype "passive"))
    )
    (net (code "9") (name "/ADC_0.2_IN") (class "Default")
      (node (ref "P6") (pin "5") (pinfunction "5_5") (pintype "passive"))
      (node (ref "R41") (pin "2") (pinfunction "2_2") (pintype "passive"))
    )
    (net (code "10") (name "/ADC_0.3") (class "Default")
      (node (ref "C42") (pin "2") (pinfunction "2_2") (pintype "passive"))
      (node (ref "D9") (pin "3") (pintype "passive"))
      (node (ref "IC1") (pin "18") (pinfunction "P0[26]__AD0[3]__AOUT/RXD3_18") (pintype "bidirectional"))
      (node (ref "R42") (pin "1") (pinfunction "1_1") (pintype "passive"))
    )
    (net (code "11") (name "/ADC_0.3_IN") (class "Default")
      (node (ref "P6") (pin "7") (pinfunction "7_7") (pintype "passive"))
      (node (ref "R42") (pin "2") (pinfunction "2_2") (pintype "passive"))
    )
    (net (code "12") (name "/ADC_0.4") (class "Default")
      (node (ref "C43") (pin "2") (pinfunction "2_2") (pintype "passive"))
      (node (ref "D10") (pin "3") (pintype "passive"))
      (node (ref "IC1") (pin "19") (pinfunction "P1[30]__VBUS__AD0[4]_19") (pintype "bidirectional"))
      (node (ref "R43") (pin "1") (pinfunction "1_1") (pintype "passive"))
    )
    (net (code "13") (name "/ADC_0.4_IN") (class "Default")
      (node (ref "P8") (pin "1") (pinfunction "1_1") (pintype "passive"))
      (node (ref "R43") (pin "2") (pinfunction "2_2") (pintype "passive"))
    )
    (net (code "14") (name "/ADC_0.5") (class "Default")
      (node (ref "C44") (pin "2") (pinfunction "2_2") (pintype "passive"))
      (node (ref "D11") (pin "3") (pintype "passive"))
      (node (ref "IC1") (pin "20") (pinfunction "P1[31]__SCK1__AD0[5]_20") (pintype "bidirectional"))
      (node (ref "R44") (pin "1") (pinfunction "1_1") (pintype "passive"))
    )
    (net (code "15") (name "/ADC_0.5_IN") (class "Default")
      (node (ref "P8") (pin "3") (pinfunction "3_3") (pintype "passive"))
      (node (ref "R44") (pin "2") (pinfunction "2_2") (pintype "passive"))
    )
    (net (code "16") (name "/ADC_0.6") (class "Default")
      (node (ref "C45") (pin "2") (pinfunction "2_2") (pintype "passive"))
      (node (ref "D12") (pin "3") (pintype "passive"))
      (node (ref "IC1") (pin "21") (pinfunction "P0[2]__TXD0__AD0[7]__21") (pintype "bidirectional"))
      (node (ref "R45") (pin "1") (pinfunction "1_1") (pintype "passive"))
    )
    (net (code "17") (name "/ADC_0.6_IN") (class "Default")
      (node (ref "P8") (pin "5") (pinfunction "5_5") (pintype "passive"))
      (node (ref "R45") (pin "2") (pinfunction "2_2") (pintype "passive"))
    )
    (net (code "18") (name "/ADC_0.7") (class "Default")
      (node (ref "C46") (pin "2") (pinfunction "2_2") (pintype "passive"))
      (node (ref "D13") (pin "3") (pintype "passive"))
      (node (ref "IC1") (pin "22") (pinfunction "P0[3]__RXD0__AD0[6]_22") (pintype "bidirectional"))
      (node (ref "R46") (pin "1") (pinfunction "1_1") (pintype "passive"))
    )
    (net (code "19") (name "/ADC_0.7_IN") (class "Default")
      (node (ref "P8") (pin "7") (pinfunction "7_7") (pintype "passive"))
      (node (ref "R46") (pin "2") (pinfunction "2_2") (pintype "passive"))
    )
    (net (code "20") (name "/DIO_CL") (class "Default")
      (node (ref "P3") (pin "1") (pinfunction "1_1") (pintype "passive"))
      (node (ref "U1") (pin "18") (pinfunction "Y1_18") (pintype "tri_state"))
    )
    (net (code "21") (name "/DIO_CL_A") (class "Default")
      (node (ref "IC1") (pin "7") (pinfunction "P0[7]__I2STX_CLK__SCK1__MAT2[1]_7") (pintype "bidirectional"))
      (node (ref "U1") (pin "2") (pinfunction "A1_2") (pintype "input"))
    )
    (net (code "22") (name "/DIO_ID") (class "Default")
      (node (ref "IC1") (pin "6") (pinfunction "P0[8]__I2STX_WS__MISO1__MAT2[2]_6") (pintype "bidirectional"))
      (node (ref "P3") (pin "5") (pinfunction "5_5") (pintype "passive"))
    )
    (net (code "23") (name "/DIO_IG") (class "Default")
      (node (ref "P3") (pin "8") (pinfunction "8_8") (pintype "passive"))
      (node (ref "U1") (pin "15") (pinfunction "Y4_15") (pintype "tri_state"))
    )
    (net (code "24") (name "/DIO_IG_A") (class "Default")
      (node (ref "IC1") (pin "68") (pinfunction "P3[26]__STCLK__MAT0[1]_(PAD14)_68") (pintype "bidirectional"))
      (node (ref "U1") (pin "5") (pinfunction "A4_5") (pintype "input"))
    )
    (net (code "25") (name "/DIO_OD") (class "Default")
      (node (ref "P3") (pin "3") (pinfunction "3_3") (pintype "passive"))
      (node (ref "U1") (pin "17") (pinfunction "Y2_17") (pintype "tri_state"))
    )
    (net (code "26") (name "/DIO_OD_A") (class "Default")
      (node (ref "IC1") (pin "5") (pinfunction "P0[9]__I2STX_SDA__MOSI1__MAT2[3]_5") (pintype "bidirectional"))
      (node (ref "U1") (pin "3") (pinfunction "A2_3") (pintype "input"))
    )
    (net (code "27") (name "/DIO_OS") (class "Default")
      (node (ref "P3") (pin "7") (pinfunction "7_7") (pintype "passive"))
      (node (ref "U1") (pin "16") (pinfunction "Y3_16") (pintype "tri_state"))
    )
    (net (code "28") (name "/DIO_OS_A") (class "Default")
      (node (ref "IC1") (pin "8") (pinfunction "P0[6]__I2SRX_SDA__SSEL1__MAT2[0]_8") (pintype "bidirectional"))
      (node (ref "U1") (pin "4") (pinfunction "A3_4") (pintype "input"))
    )
    (net (code "29") (name "/ETH_RD_N") (class "Default")
      (node (ref "IC1") (pin "32") (pinfunction "RD-_(Ethernet)_32") (pintype "bidirectional"))
      (node (ref "P17") (pin "5") (pinfunction "RD-_5") (pintype "passive"))
    )
    (net (code "30") (name "/ETH_RD_P") (class "Default")
      (node (ref "IC1") (pin "33") (pinfunction "RD+_(Ethernet)_33") (pintype "bidirectional"))
      (node (ref "P17") (pin "4") (pinfunction "RD+_4") (pintype "passive"))
    )
    (net (code "31") (name "/ETH_TD_N") (class "Default")
      (node (ref "IC1") (pin "34") (pinfunction "TD-_(Ethernet)_34") (pintype "bidirectional"))
      (node (ref "P17") (pin "3") (pinfunction "TD-_3") (pintype "passive"))
    )
    (net (code "32") (name "/ETH_TD_P") (class "Default")
      (node (ref "IC1") (pin "35") (pinfunction "TD+_(Ethernet)_35") (pintype "bidirectional"))
      (node (ref "P17") (pin "1") (pinfunction "TD+_1") (pintype "passive"))
    )
    (net (code "33") (name "/JTAG_RST") (class "Default")
      (node (ref "IC1") (pin "79") (pinfunction "JTAG_RESET_(J4.12)_79") (pintype "passive"))
      (node (ref "P1b") (pin "10") (pinfunction "10_10") (pintype "passive"))
    )
    (net (code "34") (name "/JTAG_RTCK") (class "Default")
      (node (ref "P1b") (pin "7") (pinfunction "7_7") (pintype "passive"))
      (node (ref "R1") (pin "1") (pinfunction "1_1") (pintype "passive"))
    )
    (net (code "35") (name "/JTAG_TDI") (class "Default")
      (node (ref "IC1") (pin "78") (pinfunction "JTAG_TDI_(J4.10)_78") (pintype "passive"))
      (node (ref "P1b") (pin "8") (pinfunction "8_8") (pintype "passive"))
    )
    (net (code "36") (name "/JTAG_TDO") (class "Default")
      (node (ref "IC1") (pin "77") (pinfunction "JTAG_TDO_SWO_(J4.8)_77") (pintype "passive"))
      (node (ref "P1b") (pin "6") (pinfunction "6_6") (pintype "passive"))
    )
    (net (code "37") (name "/JTAG_TMS") (class "Default")
      (node (ref "IC1") (pin "75") (pinfunction "JTAG_TMS_SWDIO_(J4.4)_75") (pintype "passive"))
      (node (ref "P1b") (pin "2") (pinfunction "2_2") (pintype "passive"))
    )
    (net (code "38") (name "/KEY_0") (class "Default")
      (node (ref "IC1") (pin "42") (pinfunction "P2[0]__PWM1[1]__TXD1_42") (pintype "bidirectional"))
      (node (ref "P13") (pin "2") (pinfunction "2_2") (pintype "passive"))
      (node (ref "P15") (pin "2") (pinfunction "2_2") (pintype "passive"))
      (node (ref "R2") (pin "2") (pinfunction "2_2") (pintype "passive"))
    )
    (net (code "39") (name "/KEY_1") (class "Default")
      (node (ref "IC1") (pin "43") (pinfunction "P2[1]__PWM1[2]__RXD1_43") (pintype "bidirectional"))
      (node (ref "P13") (pin "4") (pinfunction "4_4") (pintype "passive"))
      (node (ref "P15") (pin "4") (pinfunction "4_4") (pintype "passive"))
      (node (ref "R3") (pin "2") (pinfunction "2_2") (pintype "passive"))
    )
    (net (code "40") (name "/KEY_2") (class "Default")
      (node (ref "IC1") (pin "44") (pinfunction "P2[2]__PWM1[3]__CTS1__TRACEDATA[3]_44") (pintype "bidirectional"))
      (node (ref "P13") (pin "6") (pinfunction "6_6") (pintype "passive"))
      (node (ref "P15") (pin "6") (pinfunction "6_6") (pintype "passive"))
      (node (ref "R4") (pin "2") (pinfunction "2_2") (pintype "passive"))
    )
    (net (code "41") (name "/KEY_3") (class "Default")
      (node (ref "IC1") (pin "45") (pinfunction "P2[3]__PWM1[4]__DCD1__TRACEDATA[2]_45") (pintype "bidirectional"))
      (node (ref "P13") (pin "8") (pinfunction "8_8") (pintype "passive"))
      (node (ref "P15") (pin "8") (pinfunction "8_8") (pintype "passive"))
      (node (ref "R5") (pin "2") (pinfunction "2_2") (pintype "passive"))
    )
    (net (code "42") (name "/KEY_4") (class "Default")
      (node (ref "IC1") (pin "46") (pinfunction "P2[4]__PWM1[5]__DSR1__TRACEDATA[1]_46") (pintype "bidirectional"))
      (node (ref "P13") (pin "10") (pinfunction "10_10") (pintype "passive"))
      (node (ref "P15") (pin "10") (pinfunction "10_10") (pintype "passive"))
      (node (ref "R6") (pin "2") (pinfunction "2_2") (pintype "passive"))
    )
    (net (code "43") (name "/KEY_5") (class "Default")
      (node (ref "IC1") (pin "47") (pinfunction "P2[5]__PWM1[6]__DTR1__TRACEDATA[0]_47") (pintype "bidirectional"))
      (node (ref "P13") (pin "12") (pinfunction "12_12") (pintype "passive"))
      (node (ref "P15") (pin "12") (pinfunction "12_12") (pintype "passive"))
      (node (ref "R8") (pin "2") (pinfunction "2_2") (pintype "passive"))
    )
    (net (code "44") (name "/KEY_6") (class "Default")
      (node (ref "IC1") (pin "48") (pinfunction "P2[6]__PCAP1[0]__RI1__TRACECLK_48") (pintype "bidirectional"))
      (node (ref "P13") (pin "14") (pinfunction "14_14") (pintype "passive"))
      (node (ref "P15") (pin "14") (pinfunction "14_14") (pintype "passive"))
      (node (ref "R7") (pin "2") (pinfunction "2_2") (pintype "passive"))
    )
    (net (code "45") (name "/KEY_7") (class "Default")
      (node (ref "IC1") (pin "49") (pinfunction "P2[7]__RD2__RTS1_49") (pintype "bidirectional"))
      (node (ref "P13") (pin "16") (pinfunction "16_16") (pintype "passive"))
      (node (ref "P15") (pin "16") (pinfunction "16_16") (pintype "passive"))
      (node (ref "R9") (pin "2") (pinfunction "2_2") (pintype "passive"))
    )
    (net (code "46") (name "/LCD1_E") (class "Default")
      (node (ref "IC1") (pin "66") (pinfunction "P1[29]__MCOB2__PCAP1[1]__MAT0[1]_(PAD12)_66") (pintype "bidirectional"))
      (node (ref "P14") (pin "12") (pinfunction "12_12") (pintype "passive"))
      (node (ref "R22") (pin "2") (pinfunction "2_2") (pintype "passive"))
    )
    (net (code "47") (name "/LCD2_E") (class "Default")
      (node (ref "IC1") (pin "67") (pinfunction "P3[25]__MAT0[0]__PWM1[2]_(PAD13)_67") (pintype "bidirectional"))
      (node (ref "P16") (pin "12") (pinfunction "12_12") (pintype "passive"))
      (node (ref "R21") (pin "2") (pinfunction "2_2") (pintype "passive"))
    )
    (net (code "48") (name "/LCD_B-") (class "Default")
      (node (ref "P14") (pin "2") (pinfunction "2_2") (pintype "passive"))
      (node (ref "P16") (pin "2") (pinfunction "2_2") (pintype "passive"))
      (node (ref "Q1") (pin "1") (pinfunction "C_1") (pintype "passive"))
      (node (ref "R14") (pin "1") (pinfunction "1_1") (pintype "passive"))
    )
    (net (code "49") (name "/LCD_D0") (class "Default")
      (node (ref "P14") (pin "9") (pinfunction "9_9") (pintype "passive"))
      (node (ref "P16") (pin "9") (pinfunction "9_9") (pintype "passive"))
      (node (ref "U2") (pin "15") (pinfunction "QA_15") (pintype "tri_state"))
    )
    (net (code "50") (name "/LCD_D1") (class "Default")
      (node (ref "P14") (pin "10") (pinfunction "10_10") (pintype "passive"))
      (node (ref "P16") (pin "10") (pinfunction "10_10") (pintype "passive"))
      (node (ref "U2") (pin "1") (pinfunction "QB_1") (pintype "tri_state"))
    )
    (net (code "51") (name "/LCD_D2") (class "Default")
      (node (ref "P14") (pin "7") (pinfunction "7_7") (pintype "passive"))
      (node (ref "P16") (pin "7") (pinfunction "7_7") (pintype "passive"))
      (node (ref "U2") (pin "2") (pinfunction "QC_2") (pintype "tri_state"))
    )
    (net (code "52") (name "/LCD_D3") (class "Default")
      (node (ref "P14") (pin "8") (pinfunction "8_8") (pintype "passive"))
      (node (ref "P16") (pin "8") (pinfunction "8_8") (pintype "passive"))
      (node (ref "U2") (pin "3") (pinfunction "QD_3") (pintype "tri_state"))
    )
    (net (code "53") (name "/LCD_D4") (class "Default")
      (node (ref "P14") (pin "5") (pinfunction "5_5") (pintype "passive"))
      (node (ref "P16") (pin "5") (pinfunction "5_5") (pintype "passive"))
      (node (ref "U2") (pin "4") (pinfunction "QE_4") (pintype "tri_state"))
    )
    (net (code "54") (name "/LCD_D5") (class "Default")
      (node (ref "P14") (pin "6") (pinfunction "6_6") (pintype "passive"))
      (node (ref "P16") (pin "6") (pinfunction "6_6") (pintype "passive"))
      (node (ref "U2") (pin "5") (pinfunction "QF_5") (pintype "tri_state"))
    )
    (net (code "55") (name "/LCD_D6") (class "Default")
      (node (ref "P14") (pin "3") (pinfunction "3_3") (pintype "passive"))
      (node (ref "P16") (pin "3") (pinfunction "3_3") (pintype "passive"))
      (node (ref "U2") (pin "6") (pinfunction "QG_6") (pintype "tri_state"))
    )
    (net (code "56") (name "/LCD_D7") (class "Default")
      (node (ref "IC1") (pin "56") (pinfunction "P1[19]__MCOA0__USB_PPWR__CAP1[1]_(PAD2)_56") (pintype "bidirectional"))
      (node (ref "P14") (pin "4") (pinfunction "4_4") (pintype "passive"))
      (node (ref "P16") (pin "4") (pinfunction "4_4") (pintype "passive"))
      (node (ref "U2") (pin "7") (pinfunction "QH_7") (pintype "tri_state"))
    )
    (net (code "57") (name "/LCD_DRIVER_CL") (class "Default")
      (node (ref "IC1") (pin "62") (pinfunction "P1[25]__MCOA1__MAT1[1]_(PAD8)_62") (pintype "bidirectional"))
      (node (ref "U2") (pin "11") (pinfunction "SRCLK_11") (pintype "input"))
    )
    (net (code "58") (name "/LCD_DRIVER_OD") (class "Default")
      (node (ref "IC1") (pin "65") (pinfunction "P1[28]__MCOA2__PCAP1[0]__MAT0[0]_(PAD11)_65") (pintype "bidirectional"))
      (node (ref "U2") (pin "14") (pinfunction "SER_14") (pintype "input"))
    )
    (net (code "59") (name "/LCD_DRIVER_OE") (class "Default")
      (node (ref "IC1") (pin "64") (pinfunction "P1[27]__CLKOUT__USB_OVRCR__CAP0[1]_(PAD10)_64") (pintype "bidirectional"))
      (node (ref "U2") (pin "13") (pinfunction "~{OE}_13") (pintype "input"))
    )
    (net (code "60") (name "/LCD_DRIVER_OS") (class "Default")
      (node (ref "IC1") (pin "63") (pinfunction "P1[26]__MCOB1__PWM1[6]__CAP0[0]_(PAD9)_63") (pintype "bidirectional"))
      (node (ref "U2") (pin "12") (pinfunction "RCLK_12") (pintype "input"))
    )
    (net (code "61") (name "/LCD_RS") (class "Default")
      (node (ref "P14") (pin "14") (pinfunction "14_14") (pintype "passive"))
      (node (ref "P16") (pin "14") (pinfunction "14_14") (pintype "passive"))
      (node (ref "R20") (pin "2") (pinfunction "2_2") (pintype "passive"))
    )
    (net (code "62") (name "/LCD_RW") (class "Default")
      (node (ref "P14") (pin "11") (pinfunction "11_11") (pintype "passive"))
      (node (ref "P16") (pin "11") (pinfunction "11_11") (pintype "passive"))
      (node (ref "R19") (pin "2") (pinfunction "2_2") (pintype "passive"))
    )
    (net (code "63") (name "/LCD_V0") (class "Default")
      (node (ref "P14") (pin "13") (pinfunction "13_13") (pintype "passive"))
      (node (ref "P16") (pin "13") (pinfunction "13_13") (pintype "passive"))
      (node (ref "R15") (pin "W") (pinfunction "W_W") (pintype "passive"))
    )
    (net (code "64") (name "/LINE_0") (class "Default")
      (node (ref "R23") (pin "2") (pinfunction "2_2") (pintype "passive"))
      (node (ref "U3") (pin "1") (pinfunction "~{Y}0_1") (pintype "output"))
    )
    (net (code "65") (name "/LINE_1") (class "Default")
      (node (ref "R24") (pin "2") (pinfunction "2_2") (pintype "passive"))
      (node (ref "U3") (pin "2") (pinfunction "~{Y}1_2") (pintype "output"))
    )
    (net (code "66") (name "/LINE_2") (class "Default")
      (node (ref "R25") (pin "2") (pinfunction "2_2") (pintype "passive"))
      (node (ref "U3") (pin "3") (pinfunction "~{Y}2_3") (pintype "output"))
    )
    (net (code "67") (name "/LINE_3") (class "Default")
      (node (ref "R26") (pin "2") (pinfunction "2_2") (pintype "passive"))
      (node (ref "U3") (pin "4") (pinfunction "~{Y}3_4") (pintype "output"))
    )
    (net (code "68") (name "/LINE_4") (class "Default")
      (node (ref "R27") (pin "2") (pinfunction "2_2") (pintype "passive"))
      (node (ref "U3") (pin "5") (pinfunction "~{Y}4_5") (pintype "output"))
    )
    (net (code "69") (name "/LINE_5") (class "Default")
      (node (ref "R28") (pin "2") (pinfunction "2_2") (pintype "passive"))
      (node (ref "U3") (pin "6") (pinfunction "~{Y}5_6") (pintype "output"))
    )
    (net (code "70") (name "/LINE_6") (class "Default")
      (node (ref "R29") (pin "2") (pinfunction "2_2") (pintype "passive"))
      (node (ref "U3") (pin "7") (pinfunction "~{Y}6_7") (pintype "output"))
    )
    (net (code "71") (name "/LINE_7") (class "Default")
      (node (ref "R30") (pin "2") (pinfunction "2_2") (pintype "passive"))
      (node (ref "U3") (pin "8") (pinfunction "~{Y}7_8") (pintype "output"))
    )
    (net (code "72") (name "/LINE_8") (class "Default")
      (node (ref "R31") (pin "2") (pinfunction "2_2") (pintype "passive"))
      (node (ref "U3") (pin "9") (pinfunction "~{Y}8_9") (pintype "output"))
    )
    (net (code "73") (name "/LINE_9") (class "Default")
      (node (ref "R32") (pin "2") (pinfunction "2_2") (pintype "passive"))
      (node (ref "U3") (pin "10") (pinfunction "~{Y}9_10") (pintype "output"))
    )
    (net (code "74") (name "/LINE_10") (class "Default")
      (node (ref "R33") (pin "2") (pinfunction "2_2") (pintype "passive"))
      (node (ref "U3") (pin "11") (pinfunction "~{Y}10_11") (pintype "output"))
    )
    (net (code "75") (name "/LINE_11") (class "Default")
      (node (ref "R34") (pin "2") (pinfunction "2_2") (pintype "passive"))
      (node (ref "U3") (pin "13") (pinfunction "~{Y}11_13") (pintype "output"))
    )
    (net (code "76") (name "/LINE_12") (class "Default")
      (node (ref "R35") (pin "2") (pinfunction "2_2") (pintype "passive"))
      (node (ref "U3") (pin "14") (pinfunction "~{Y}12_14") (pintype "output"))
    )
    (net (code "77") (name "/LINE_13") (class "Default")
      (node (ref "R36") (pin "2") (pinfunction "2_2") (pintype "passive"))
      (node (ref "U3") (pin "15") (pinfunction "~{Y}13_15") (pintype "output"))
    )
    (net (code "78") (name "/LINE_14") (class "Default")
      (node (ref "R37") (pin "2") (pinfunction "2_2") (pintype "passive"))
      (node (ref "U3") (pin "16") (pinfunction "~{Y}14_16") (pintype "output"))
    )
    (net (code "79") (name "/LINE_15") (class "Default")
      (node (ref "R38") (pin "2") (pinfunction "2_2") (pintype "passive"))
      (node (ref "U3") (pin "17") (pinfunction "~{Y}15_17") (pintype "output"))
    )
    (net (code "80") (name "/LINE_A") (class "Default")
      (node (ref "IC1") (pin "57") (pinfunction "P1[20]__MCI0__PWM1[2]__SCK0_(PAD3)_57") (pintype "bidirectional"))
      (node (ref "U3") (pin "23") (pinfunction "A_23") (pintype "input"))
    )
    (net (code "81") (name "/LINE_B") (class "Default")
      (node (ref "IC1") (pin "58") (pinfunction "P1[21]__MCABORT__PWM1[3]__SSEL0_(PAD4)_58") (pintype "bidirectional"))
      (node (ref "U3") (pin "22") (pinfunction "B_22") (pintype "input"))
    )
    (net (code "82") (name "/LINE_C") (class "Default")
      (node (ref "IC1") (pin "59") (pinfunction "P1[22]__MCOB0__USB_PWRD__MAT1[0]_(PAD5)_59") (pintype "bidirectional"))
      (node (ref "U3") (pin "21") (pinfunction "C_21") (pintype "input"))
    )
    (net (code "83") (name "/LINE_D") (class "Default")
      (node (ref "IC1") (pin "60") (pinfunction "P1[23]__MCI1__PWM1[4]__MISO0_(PAD6)_60") (pintype "bidirectional"))
      (node (ref "U3") (pin "20") (pinfunction "D_20") (pintype "input"))
    )
    (net (code "84") (name "/LINE_EN{slash}DIS") (class "Default")
      (node (ref "IC1") (pin "55") (pinfunction "P1[18]__USB_UP_LED__PWM1[1]__CAP1[0]_(PAD1)_55") (pintype "bidirectional"))
      (node (ref "U3") (pin "18") (pinfunction "~{OE}1_18") (pintype "input"))
    )
    (net (code "85") (name "/RXD2") (class "Default")
      (node (ref "IC1") (pin "41") (pinfunction "P0[11]__RXD2__SCL2__MAT3[1]_41") (pintype "bidirectional"))
      (node (ref "P2") (pin "4") (pinfunction "4_4") (pintype "passive"))
    )
    (net (code "86") (name "/RXD3") (class "Default")
      (node (ref "IC1") (pin "10") (pinfunction "P0[1]__TD1__RXD3__SCL1_10") (pintype "bidirectional"))
      (node (ref "P2") (pin "8") (pinfunction "8_8") (pintype "passive"))
    )
    (net (code "87") (name "/SPARE_P0.4") (class "Default")
      (node (ref "IC1") (pin "38") (pinfunction "P0[4]__I2SRX_CLK__RD2__CAP2[0]_38") (pintype "bidirectional"))
      (node (ref "P7") (pin "1") (pinfunction "1_1") (pintype "passive"))
    )
    (net (code "88") (name "/SPARE_P0.5") (class "Default")
      (node (ref "IC1") (pin "39") (pinfunction "P0[5]__I2SRX_WS__TD2__CAP2[1]_39") (pintype "bidirectional"))
      (node (ref "P7") (pin "2") (pinfunction "2_2") (pintype "passive"))
    )
    (net (code "89") (name "/SPARE_P0.22") (class "Default")
      (node (ref "IC1") (pin "24") (pinfunction "P0[22]__RTS1__TD1_24") (pintype "bidirectional"))
      (node (ref "P7") (pin "3") (pinfunction "3_3") (pintype "passive"))
    )
    (net (code "90") (name "/SPARE_P0.27") (class "Default")
      (node (ref "IC1") (pin "25") (pinfunction "P0[27]__SDA0__USB_SDA_25") (pintype "bidirectional"))
      (node (ref "P7") (pin "4") (pinfunction "4_4") (pintype "passive"))
    )
    (net (code "91") (name "/SPARE_P0.28") (class "Default")
      (node (ref "IC1") (pin "26") (pinfunction "P0[28]__SCL0__USB_SCL_26") (pintype "bidirectional"))
      (node (ref "P7") (pin "5") (pinfunction "5_5") (pintype "passive"))
    )
    (net (code "92") (name "/SPARE_P1.24") (class "Default")
      (node (ref "IC1") (pin "61") (pinfunction "P1[24]__MCI2__PWM1[5]__MOSI0_(PAD7)_61") (pintype "bidirectional"))
      (node (ref "P9") (pin "5") (pinfunction "5_5") (pintype "passive"))
    )
    (net (code "93") (name "/SPARE_P2.8") (class "Default")
      (node (ref "IC1") (pin "50") (pinfunction "P2[8]__TD2__TXD2_50") (pintype "bidirectional"))
      (node (ref "P9") (pin "1") (pinfunction "1_1") (pintype "passive"))
    )
    (net (code "94") (name "/SPARE_P2.11") (class "Default")
      (node (ref "IC1") (pin "52") (pinfunction "P2[11]__EINT1__I2STX_CLK_52") (pintype "bidirectional"))
      (node (ref "P9") (pin "2") (pinfunction "2_2") (pintype "passive"))
    )
    (net (code "95") (name "/SPARE_P2.12") (class "Default")
      (node (ref "IC1") (pin "53") (pinfunction "P2[12]__EINT2__I2STX_WS_53") (pintype "bidirectional"))
      (node (ref "P9") (pin "3") (pinfunction "3_3") (pintype "passive"))
    )
    (net (code "96") (name "/SPARE_P2.13") (class "Default")
      (node (ref "IC1") (pin "27") (pinfunction "P2[13]__EINT3__I2STX_SDA_27") (pintype "bidirectional"))
      (node (ref "P9") (pin "4") (pinfunction "4_4") (pintype "passive"))
    )
    (net (code "97") (name "/SPARE_P4.28") (class "Default")
      (node (ref "IC1") (pin "69") (pinfunction "P4[28]__RX_MCLK__MAT2[0]__TXD3_(PAD15)_69") (pintype "bidirectional"))
      (node (ref "P9") (pin "6") (pinfunction "6_6") (pintype "passive"))
    )
    (net (code "98") (name "/SPARE_P4.29") (class "Default")
      (node (ref "IC1") (pin "70") (pinfunction "P4[29]__TX_MCLK__MAT2[1]__RXD3_(PAD16)_70") (pintype "bidirectional"))
      (node (ref "P9") (pin "7") (pinfunction "7_7") (pintype "passive"))
    )
    (net (code "99") (name "/SPI_ADC_CL") (class "Default")
      (node (ref "P5") (pin "1") (pinfunction "1_1") (pintype "passive"))
      (node (ref "U1") (pin "14") (pinfunction "Y5_14") (pintype "tri_state"))
    )
    (net (code "100") (name "/SPI_ADC_CL_A") (class "Default")
      (node (ref "IC1") (pin "13") (pinfunction "P0[15]__TXD1__SCK0__SCK_13") (pintype "bidirectional"))
      (node (ref "U1") (pin "6") (pinfunction "A5_6") (pintype "input"))
    )
    (net (code "101") (name "/SPI_ADC_ID") (class "Default")
      (node (ref "IC1") (pin "12") (pinfunction "P0[17]__CTS1__MISO0__MISO_12") (pintype "bidirectional"))
      (node (ref "P5") (pin "5") (pinfunction "5_5") (pintype "passive"))
    )
    (net (code "102") (name "/SPI_ADC_IG") (class "Default")
      (node (ref "P5") (pin "8") (pinfunction "8_8") (pintype "passive"))
      (node (ref "U1") (pin "11") (pinfunction "Y8_11") (pintype "tri_state"))
    )
    (net (code "103") (name "/SPI_ADC_IG_A") (class "Default")
      (node (ref "IC1") (pin "23") (pinfunction "P0[21]__RI1__RD1_23") (pintype "bidirectional"))
      (node (ref "U1") (pin "9") (pinfunction "A8_9") (pintype "input"))
    )
    (net (code "104") (name "/SPI_ADC_OD") (class "Default")
      (node (ref "P5") (pin "3") (pinfunction "3_3") (pintype "passive"))
      (node (ref "U1") (pin "13") (pinfunction "Y6_13") (pintype "tri_state"))
    )
    (net (code "105") (name "/SPI_ADC_OD_A") (class "Default")
      (node (ref "IC1") (pin "11") (pinfunction "P0[18]__DCD1__MOSI0__MOSI_11") (pintype "bidirectional"))
      (node (ref "U1") (pin "7") (pinfunction "A6_7") (pintype "input"))
    )
    (net (code "106") (name "/SPI_ADC_OS") (class "Default")
      (node (ref "P5") (pin "7") (pinfunction "7_7") (pintype "passive"))
      (node (ref "U1") (pin "12") (pinfunction "Y7_12") (pintype "tri_state"))
    )
    (net (code "107") (name "/SPI_ADC_OS_A") (class "Default")
      (node (ref "IC1") (pin "14") (pinfunction "P0[16]__RXD1__SSEL0__SSEL_14") (pintype "bidirectional"))
      (node (ref "U1") (pin "8") (pinfunction "A7_8") (pintype "input"))
    )
    (net (code "108") (name "/TXD2") (class "Default")
      (node (ref "IC1") (pin "40") (pinfunction "P0[10]__TXD2__SDA2__MAT3[0]_40") (pintype "bidirectional"))
      (node (ref "P2") (pin "2") (pinfunction "2_2") (pintype "passive"))
    )
    (net (code "109") (name "/TXD3") (class "Default")
      (node (ref "IC1") (pin "9") (pinfunction "P0[0]__RD1__TXD3__SDA1_9") (pintype "bidirectional"))
      (node (ref "P2") (pin "6") (pinfunction "6_6") (pintype "passive"))
    )
    (net (code "110") (name "/USB_D_N") (class "Default")
      (node (ref "IC1") (pin "36") (pinfunction "D-_(USB)_36") (pintype "bidirectional"))
      (node (ref "P4") (pin "2") (pinfunction "D-_2") (pintype "passive"))
    )
    (net (code "111") (name "/USB_D_P") (class "Default")
      (node (ref "IC1") (pin "37") (pinfunction "D+_(USB)_37") (pintype "bidirectional"))
      (node (ref "P4") (pin "3") (pinfunction "D+_3") (pintype "passive"))
    )
    (net (code "112") (name "/USB_GND") (class "Default")
      (node (ref "J14") (pin "2") (pinfunction "2_2") (pintype "passive"))
      (node (ref "P4") (pin "4") (pinfunction "GND_4") (pintype "passive"))
    )
    (net (code "113") (name "/USB_SHIELD") (class "Default")
      (node (ref "J13") (pin "2") (pinfunction "2_2") (pintype "passive"))
      (node (ref "P4") (pin "5") (pinfunction "Shield_5") (pintype "passive"))
    )
    (net (code "114") (name "/V_CLAV") (class "Default")
      (node (ref "C15") (pin "2") (pinfunction "2_2") (pintype "passive"))
      (node (ref "C16") (pin "1") (pinfunction "1_1") (pintype "passive"))
      (node (ref "J10") (pin "2") (pinfunction "2_2") (pintype "passive"))
      (node (ref "R2") (pin "1") (pinfunction "1_1") (pintype "passive"))
      (node (ref "R3") (pin "1") (pinfunction "1_1") (pintype "passive"))
      (node (ref "R4") (pin "1") (pinfunction "1_1") (pintype "passive"))
      (node (ref "R5") (pin "1") (pinfunction "1_1") (pintype "passive"))
      (node (ref "R6") (pin "1") (pinfunction "1_1") (pintype "passive"))
      (node (ref "R7") (pin "1") (pinfunction "1_1") (pintype "passive"))
      (node (ref "R8") (pin "1") (pinfunction "1_1") (pintype "passive"))
      (node (ref "R9") (pin "1") (pinfunction "1_1") (pintype "passive"))
      (node (ref "U3") (pin "24") (pinfunction "VCC_24") (pintype "power_in"))
    )
    (net (code "118") (name "3V3") (class "Default")
      (node (ref "C1") (pin "2") (pinfunction "2_2") (pintype "passive"))
      (node (ref "C2") (pin "1") (pinfunction "1_1") (pintype "passive"))
      (node (ref "D10") (pin "1") (pinfunction "1_1") (pintype "passive"))
      (node (ref "D11") (pin "1") (pinfunction "1_1") (pintype "passive"))
      (node (ref "D12") (pin "1") (pinfunction "1_1") (pintype "passive"))
      (node (ref "D13") (pin "1") (pinfunction "1_1") (pintype "passive"))
      (node (ref "D6") (pin "1") (pinfunction "1_1") (pintype "passive"))
      (node (ref "D7") (pin "1") (pinfunction "1_1") (pintype "passive"))
      (node (ref "D8") (pin "1") (pinfunction "1_1") (pintype "passive"))
      (node (ref "D9") (pin "1") (pinfunction "1_1") (pintype "passive"))
      (node (ref "IC1") (pin "28") (pinfunction "VIO_3V3_28") (pintype "power_in"))
      (node (ref "IC1") (pin "74") (pinfunction "VIO_3V3_(J4.2)_74") (pintype "passive"))
      (node (ref "J1") (pin "1") (pinfunction "1_1") (pintype "passive"))
      (node (ref "J10") (pin "1") (pinfunction "1_1") (pintype "passive"))
      (node (ref "J11") (pin "1") (pinfunction "1_1") (pintype "passive"))
      (node (ref "J4") (pin "1") (pinfunction "1_1") (pintype "passive"))
      (node (ref "J5") (pin "1") (pinfunction "1_1") (pintype "passive"))
      (node (ref "J9") (pin "2") (pinfunction "2_2") (pintype "passive"))
      (node (ref "P12") (pin "1") (pinfunction "1_1") (pintype "passive"))
      (node (ref "P6") (pin "10") (pinfunction "10_10") (pintype "passive"))
      (node (ref "P8") (pin "10") (pinfunction "10_10") (pintype "passive"))
    )
    (net (code "119") (name "5V") (class "Default")
      (node (ref "J1") (pin "3") (pinfunction "3_3") (pintype "passive"))
      (node (ref "J10") (pin "3") (pinfunction "3_3") (pintype "passive"))
      (node (ref "J11") (pin "3") (pinfunction "3_3") (pintype "passive"))
      (node (ref "J18") (pin "2") (pinfunction "2_2") (pintype "passive"))
      (node (ref "J4") (pin "3") (pinfunction "3_3") (pintype "passive"))
      (node (ref "J5") (pin "3") (pinfunction "3_3") (pintype "passive"))
      (node (ref "J7") (pin "2") (pinfunction "2_2") (pintype "passive"))
      (node (ref "P11") (pin "1") (pinfunction "1_1") (pintype "passive"))
      (node (ref "P14") (pin "1") (pinfunction "1_1") (pintype "passive"))
      (node (ref "P16") (pin "1") (pinfunction "1_1") (pintype "passive"))
      (node (ref "R14") (pin "2") (pinfunction "2_2") (pintype "passive"))
      (node (ref "R17") (pin "CW") (pinfunction "+_CW") (pintype "passive"))
    )
    (net (code "120") (name "GND") (class "Default")
      (node (ref "C1") (pin "1") (pinfunction "1_1") (pintype "passive"))
      (node (ref "C11") (pin "1") (pinfunction "1_1") (pintype "passive"))
      (node (ref "C12") (pin "1") (pinfunction "1_1") (pintype "passive"))
      (node (ref "C13") (pin "2") (pinfunction "2_2") (pintype "passive"))
      (node (ref "C14") (pin "2") (pinfunction "2_2") (pintype "passive"))
      (node (ref "C15") (pin "1") (pinfunction "1_1") (pintype "passive"))
      (node (ref "C16") (pin "2") (pinfunction "2_2") (pintype "passive"))
      (node (ref "C17") (pin "1") (pinfunction "1_1") (pintype "passive"))
      (node (ref "C18") (pin "1") (pinfunction "1_1") (pintype "passive"))
      (node (ref "C2") (pin "2") (pinfunction "2_2") (pintype "passive"))
      (node (ref "C20") (pin "2") (pinfunction "2_2") (pintype "passive"))
      (node (ref "C21") (pin "1") (pinfunction "1_1") (pintype "passive"))
      (node (ref "C22") (pin "1") (pinfunction "1_1") (pintype "passive"))
      (node (ref "C23") (pin "1") (pinfunction "1_1") (pintype "passive"))
      (node (ref "C24") (pin "1") (pinfunction "1_1") (pintype "passive"))
      (node (ref "C25") (pin "1") (pinfunction "1_1") (pintype "passive"))
      (node (ref "C26") (pin "1") (pinfunction "1_1") (pintype "passive"))
      (node (ref "C27") (pin "1") (pinfunction "1_1") (pintype "passive"))
      (node (ref "C28") (pin "1") (pinfunction "1_1") (pintype "passive"))
      (node (ref "C29") (pin "1") (pinfunction "1_1") (pintype "passive"))
      (node (ref "C3") (pin "1") (pinfunction "1_1") (pintype "passive"))
      (node (ref "C30") (pin "1") (pinfunction "1_1") (pintype "passive"))
      (node (ref "C31") (pin "1") (pinfunction "1_1") (pintype "passive"))
      (node (ref "C32") (pin "1") (pinfunction "1_1") (pintype "passive"))
      (node (ref "C33") (pin "1") (pinfunction "1_1") (pintype "passive"))
      (node (ref "C34") (pin "1") (pinfunction "1_1") (pintype "passive"))
      (node (ref "C35") (pin "1") (pinfunction "1_1") (pintype "passive"))
      (node (ref "C36") (pin "1") (pinfunction "1_1") (pintype "passive"))
      (node (ref "C37") (pin "1") (pinfunction "1_1") (pintype "passive"))
      (node (ref "C38") (pin "1") (pinfunction "1_1") (pintype "passive"))
      (node (ref "C39") (pin "1") (pinfunction "1_1") (pintype "passive"))
      (node (ref "C4") (pin "1") (pinfunction "1_1") (pintype "passive"))
      (node (ref "C40") (pin "1") (pinfunction "1_1") (pintype "passive"))
      (node (ref "C41") (pin "1") (pinfunction "1_1") (pintype "passive"))
      (node (ref "C42") (pin "1") (pinfunction "1_1") (pintype "passive"))
      (node (ref "C43") (pin "1") (pinfunction "1_1") (pintype "passive"))
      (node (ref "C44") (pin "1") (pinfunction "1_1") (pintype "passive"))
      (node (ref "C45") (pin "1") (pinfunction "1_1") (pintype "passive"))
      (node (ref "C46") (pin "1") (pinfunction "1_1") (pintype "passive"))
      (node (ref "D1") (pin "2") (pinfunction "K_2") (pintype "passive"))
      (node (ref "D10") (pin "2") (pinfunction "2_2") (pintype "passive"))
      (node (ref "D11") (pin "2") (pinfunction "2_2") (pintype "passive"))
      (node (ref "D12") (pin "2") (pinfunction "2_2") (pintype "passive"))
      (node (ref "D13") (pin "2") (pinfunction "2_2") (pintype "passive"))
      (node (ref "D2") (pin "2") (pinfunction "K_2") (pintype "passive"))
      (node (ref "D3") (pin "2") (pinfunction "V-_2") (pintype "passive"))
      (node (ref "D4") (pin "2") (pinfunction "K_2") (pintype "passive"))
      (node (ref "D5") (pin "2") (pinfunction "K_2") (pintype "passive"))
      (node (ref "D6") (pin "2") (pinfunction "2_2") (pintype "passive"))
      (node (ref "D7") (pin "2") (pinfunction "2_2") (pintype "passive"))
      (node (ref "D8") (pin "2") (pinfunction "2_2") (pintype "passive"))
      (node (ref "D9") (pin "2") (pinfunction "2_2") (pintype "passive"))
      (node (ref "IC1") (pin "1") (pinfunction "GND_1") (pintype "power_in"))
      (node (ref "IC1") (pin "54") (pinfunction "GND_54") (pintype "power_in"))
      (node (ref "IC1") (pin "81") (pinfunction "GND_(J4.16)_81") (pintype "passive"))
      (node (ref "J13") (pin "1") (pinfunction "1_1") (pintype "passive"))
      (node (ref "J14") (pin "1") (pinfunction "1_1") (pintype "passive"))
      (node (ref "J16") (pin "2") (pinfunction "2_2") (pintype "passive"))
      (node (ref "J17") (pin "2") (pinfunction "2_2") (pintype "passive"))
      (node (ref "P11") (pin "2") (pinfunction "2_2") (pintype "passive"))
      (node (ref "P12") (pin "2") (pinfunction "2_2") (pintype "passive"))
      (node (ref "P14") (pin "15") (pinfunction "15_15") (pintype "passive"))
      (node (ref "P16") (pin "15") (pinfunction "15_15") (pintype "passive"))
      (node (ref "P1b") (pin "3") (pinfunction "3_3") (pintype "passive"))
      (node (ref "P1b") (pin "5") (pinfunction "5_5") (pintype "passive"))
      (node (ref "P1b") (pin "9") (pinfunction "9_9") (pintype "passive"))
      (node (ref "P2") (pin "1") (pinfunction "1_1") (pintype "passive"))
      (node (ref "P2") (pin "3") (pinfunction "3_3") (pintype "passive"))
      (node (ref "P2") (pin "5") (pinfunction "5_5") (pintype "passive"))
      (node (ref "P2") (pin "7") (pinfunction "7_7") (pintype "passive"))
      (node (ref "P2") (pin "9") (pinfunction "9_9") (pintype "passive"))
      (node (ref "P3") (pin "2") (pinfunction "2_2") (pintype "passive"))
      (node (ref "P3") (pin "4") (pinfunction "4_4") (pintype "passive"))
      (node (ref "P3") (pin "6") (pinfunction "6_6") (pintype "passive"))
      (node (ref "P3") (pin "9") (pinfunction "9_9") (pintype "passive"))
      (node (ref "P5") (pin "2") (pinfunction "2_2") (pintype "passive"))
      (node (ref "P5") (pin "4") (pinfunction "4_4") (pintype "passive"))
      (node (ref "P5") (pin "6") (pinfunction "6_6") (pintype "passive"))
      (node (ref "P5") (pin "9") (pinfunction "9_9") (pintype "passive"))
      (node (ref "P6") (pin "2") (pinfunction "2_2") (pintype "passive"))
      (node (ref "P6") (pin "4") (pinfunction "4_4") (pintype "passive"))
      (node (ref "P6") (pin "6") (pinfunction "6_6") (pintype "passive"))
      (node (ref "P6") (pin "8") (pinfunction "8_8") (pintype "passive"))
      (node (ref "P6") (pin "9") (pinfunction "9_9") (pintype "passive"))
      (node (ref "P7") (pin "9") (pinfunction "9_9") (pintype "passive"))
      (node (ref "P8") (pin "2") (pinfunction "2_2") (pintype "passive"))
      (node (ref "P8") (pin "4") (pinfunction "4_4") (pintype "passive"))
      (node (ref "P8") (pin "6") (pinfunction "6_6") (pintype "passive"))
      (node (ref "P8") (pin "8") (pinfunction "8_8") (pintype "passive"))
      (node (ref "P8") (pin "9") (pinfunction "9_9") (pintype "passive"))
      (node (ref "P9") (pin "9") (pinfunction "9_9") (pintype "passive"))
      (node (ref "Q1") (pin "3") (pinfunction "E_3") (pintype "passive"))
      (node (ref "R1") (pin "2") (pinfunction "2_2") (pintype "passive"))
      (node (ref "R15") (pin "CCW") (pinfunction "-_CCW") (pintype "passive"))
      (node (ref "R17") (pin "CCW") (pinfunction "-_CCW") (pintype "passive"))
      (node (ref "SW1") (pin "3") (pinfunction "3_3") (pintype "passive"))
      (node (ref "SW1") (pin "4") (pinfunction "4_4") (pintype "passive"))
      (node (ref "SW2") (pin "3") (pinfunction "3_3") (pintype "passive"))
      (node (ref "SW2") (pin "4") (pinfunction "4_4") (pintype "passive"))
      (node (ref "SW3") (pin "3") (pinfunction "3_3") (pintype "passive"))
      (node (ref "SW3") (pin "4") (pinfunction "4_4") (pintype "passive"))
      (node (ref "U1") (pin "1") (pinfunction "~{OE}1_1") (pintype "input"))
      (node (ref "U1") (pin "10") (pinfunction "GND_10") (pintype "power_in"))
      (node (ref "U1") (pin "19") (pinfunction "~{OE}2_19") (pintype "input"))
      (node (ref "U2") (pin "8") (pinfunction "GND_8") (pintype "power_in"))
      (node (ref "U3") (pin "12") (pinfunction "GND_12") (pintype "power_in"))
      (node (ref "U3") (pin "19") (pinfunction "~{OE}2_19") (pintype "input"))
      (node (ref "VR1") (pin "1") (pinfunction "GND_1") (pintype "power_in"))
      (node (ref "VR2") (pin "1") (pinfunction "GND_1") (pintype "power_in"))
    )
    (net (code "121") (name "Net-(C12-Pad2)") (class "Default")
      (node (ref "C12") (pin "2") (pinfunction "2_2") (pintype "passive"))
      (node (ref "C14") (pin "1") (pinfunction "1_1") (pintype "passive"))
      (node (ref "J7") (pin "1") (pinfunction "1_1") (pintype "passive"))
      (node (ref "R13") (pin "2") (pinfunction "2_2") (pintype "passive"))
      (node (ref "VR1") (pin "2") (pinfunction "Vout_2") (pintype "power_in"))
      (node (ref "VR1") (pin "4") (pinfunction "Vout_4") (pintype "power_in"))
    )
    (net (code "122") (name "Net-(C18-Pad2)") (class "Default")
      (node (ref "C18") (pin "2") (pinfunction "2_2") (pintype "passive"))
      (node (ref "C20") (pin "1") (pinfunction "1_1") (pintype "passive"))
      (node (ref "J9") (pin "1") (pinfunction "1_1") (pintype "passive"))
      (node (ref "R18") (pin "2") (pinfunction "2_2") (pintype "passive"))
      (node (ref "VR2") (pin "2") (pinfunction "Vout_2") (pintype "power_in"))
      (node (ref "VR2") (pin "4") (pinfunction "Vout_4") (pintype "power_in"))
    )
    (net (code "123") (name "Net-(C23-Pad2)") (class "Default")
      (node (ref "C23") (pin "2") (pinfunction "2_2") (pintype "passive"))
      (node (ref "P13") (pin "1") (pinfunction "1_1") (pintype "passive"))
      (node (ref "R23") (pin "1") (pinfunction "1_1") (pintype "passive"))
    )
    (net (code "124") (name "Net-(C24-Pad2)") (class "Default")
      (node (ref "C24") (pin "2") (pinfunction "2_2") (pintype "passive"))
      (node (ref "P13") (pin "3") (pinfunction "3_3") (pintype "passive"))
      (node (ref "R24") (pin "1") (pinfunction "1_1") (pintype "passive"))
    )
    (net (code "125") (name "Net-(C25-Pad2)") (class "Default")
      (node (ref "C25") (pin "2") (pinfunction "2_2") (pintype "passive"))
      (node (ref "P13") (pin "5") (pinfunction "5_5") (pintype "passive"))
      (node (ref "R25") (pin "1") (pinfunction "1_1") (pintype "passive"))
    )
    (net (code "126") (name "Net-(C26-Pad2)") (class "Default")
      (node (ref "C26") (pin "2") (pinfunction "2_2") (pintype "passive"))
      (node (ref "P13") (pin "7") (pinfunction "7_7") (pintype "passive"))
      (node (ref "R26") (pin "1") (pinfunction "1_1") (pintype "passive"))
    )
    (net (code "127") (name "Net-(C27-Pad2)") (class "Default")
      (node (ref "C27") (pin "2") (pinfunction "2_2") (pintype "passive"))
      (node (ref "P13") (pin "9") (pinfunction "9_9") (pintype "passive"))
      (node (ref "R27") (pin "1") (pinfunction "1_1") (pintype "passive"))
    )
    (net (code "128") (name "Net-(C28-Pad2)") (class "Default")
      (node (ref "C28") (pin "2") (pinfunction "2_2") (pintype "passive"))
      (node (ref "P13") (pin "11") (pinfunction "11_11") (pintype "passive"))
      (node (ref "R28") (pin "1") (pinfunction "1_1") (pintype "passive"))
    )
    (net (code "129") (name "Net-(C29-Pad2)") (class "Default")
      (node (ref "C29") (pin "2") (pinfunction "2_2") (pintype "passive"))
      (node (ref "P13") (pin "13") (pinfunction "13_13") (pintype "passive"))
      (node (ref "R29") (pin "1") (pinfunction "1_1") (pintype "passive"))
    )
    (net (code "130") (name "Net-(C30-Pad2)") (class "Default")
      (node (ref "C30") (pin "2") (pinfunction "2_2") (pintype "passive"))
      (node (ref "P13") (pin "15") (pinfunction "15_15") (pintype "passive"))
      (node (ref "R30") (pin "1") (pinfunction "1_1") (pintype "passive"))
    )
    (net (code "131") (name "Net-(C31-Pad2)") (class "Default")
      (node (ref "C31") (pin "2") (pinfunction "2_2") (pintype "passive"))
      (node (ref "P15") (pin "1") (pinfunction "1_1") (pintype "passive"))
      (node (ref "R31") (pin "1") (pinfunction "1_1") (pintype "passive"))
    )
    (net (code "132") (name "Net-(C32-Pad2)") (class "Default")
      (node (ref "C32") (pin "2") (pinfunction "2_2") (pintype "passive"))
      (node (ref "P15") (pin "3") (pinfunction "3_3") (pintype "passive"))
      (node (ref "R32") (pin "1") (pinfunction "1_1") (pintype "passive"))
    )
    (net (code "133") (name "Net-(C33-Pad2)") (class "Default")
      (node (ref "C33") (pin "2") (pinfunction "2_2") (pintype "passive"))
      (node (ref "P15") (pin "5") (pinfunction "5_5") (pintype "passive"))
      (node (ref "R33") (pin "1") (pinfunction "1_1") (pintype "passive"))
    )
    (net (code "134") (name "Net-(C34-Pad2)") (class "Default")
      (node (ref "C34") (pin "2") (pinfunction "2_2") (pintype "passive"))
      (node (ref "P15") (pin "7") (pinfunction "7_7") (pintype "passive"))
      (node (ref "R34") (pin "1") (pinfunction "1_1") (pintype "passive"))
    )
    (net (code "135") (name "Net-(C35-Pad2)") (class "Default")
      (node (ref "C35") (pin "2") (pinfunction "2_2") (pintype "passive"))
      (node (ref "P15") (pin "9") (pinfunction "9_9") (pintype "passive"))
      (node (ref "R35") (pin "1") (pinfunction "1_1") (pintype "passive"))
    )
    (net (code "136") (name "Net-(C36-Pad2)") (class "Default")
      (node (ref "C36") (pin "2") (pinfunction "2_2") (pintype "passive"))
      (node (ref "P15") (pin "11") (pinfunction "11_11") (pintype "passive"))
      (node (ref "R36") (pin "1") (pinfunction "1_1") (pintype "passive"))
    )
    (net (code "137") (name "Net-(C37-Pad2)") (class "Default")
      (node (ref "C37") (pin "2") (pinfunction "2_2") (pintype "passive"))
      (node (ref "P15") (pin "13") (pinfunction "13_13") (pintype "passive"))
      (node (ref "R37") (pin "1") (pinfunction "1_1") (pintype "passive"))
    )
    (net (code "138") (name "Net-(C38-Pad2)") (class "Default")
      (node (ref "C38") (pin "2") (pinfunction "2_2") (pintype "passive"))
      (node (ref "P15") (pin "15") (pinfunction "15_15") (pintype "passive"))
      (node (ref "R38") (pin "1") (pinfunction "1_1") (pintype "passive"))
    )
    (net (code "139") (name "Net-(D1-A)") (class "Default")
      (node (ref "D1") (pin "1") (pinfunction "A_1") (pintype "passive"))
      (node (ref "R11") (pin "1") (pinfunction "1_1") (pintype "passive"))
    )
    (net (code "140") (name "Net-(D2-A)") (class "Default")
      (node (ref "D2") (pin "1") (pinfunction "A_1") (pintype "passive"))
      (node (ref "R12") (pin "1") (pinfunction "1_1") (pintype "passive"))
    )
    (net (code "141") (name "Net-(D3-AC-Pad3)") (class "Default")
      (node (ref "D3") (pin "3") (pinfunction "AC_3") (pintype "passive"))
      (node (ref "P10") (pin "2") (pinfunction "2_2") (pintype "passive"))
    )
    (net (code "142") (name "Net-(D3-AC-Pad4)") (class "Default")
      (node (ref "D3") (pin "4") (pinfunction "AC_4") (pintype "passive"))
      (node (ref "P10") (pin "1") (pinfunction "1_1") (pintype "passive"))
    )
    (net (code "143") (name "Net-(D3-V+)") (class "Default")
      (node (ref "C13") (pin "1") (pinfunction "1_1") (pintype "passive"))
      (node (ref "D3") (pin "1") (pinfunction "V+_1") (pintype "passive"))
      (node (ref "J6") (pin "1") (pinfunction "1_1") (pintype "passive"))
      (node (ref "J8") (pin "1") (pinfunction "1_1") (pintype "passive"))
    )
    (net (code "144") (name "Net-(D4-A)") (class "Default")
      (node (ref "D4") (pin "1") (pinfunction "A_1") (pintype "passive"))
      (node (ref "R13") (pin "1") (pinfunction "1_1") (pintype "passive"))
    )
    (net (code "145") (name "Net-(D5-A)") (class "Default")
      (node (ref "D5") (pin "1") (pinfunction "A_1") (pintype "passive"))
      (node (ref "R18") (pin "1") (pinfunction "1_1") (pintype "passive"))
    )
    (net (code "146") (name "Net-(IC1-JTAG_TCLK_SWCLK_(J4.6))") (class "Default")
      (node (ref "IC1") (pin "76") (pinfunction "JTAG_TCLK_SWCLK_(J4.6)_76") (pintype "passive"))
      (node (ref "P1b") (pin "4") (pinfunction "4_4") (pintype "passive"))
    )
    (net (code "147") (name "Net-(IC1-P0[19]__DSR1__SDA1_(PAD17))") (class "Default")
      (node (ref "IC1") (pin "71") (pinfunction "P0[19]__DSR1__SDA1_(PAD17)_71") (pintype "bidirectional"))
      (node (ref "R12") (pin "2") (pinfunction "2_2") (pintype "passive"))
    )
    (net (code "148") (name "Net-(IC1-P0[20]__DTR1__SCL1_(PAD18))") (class "Default")
      (node (ref "IC1") (pin "72") (pinfunction "P0[20]__DTR1__SCL1_(PAD18)_72") (pintype "bidirectional"))
      (node (ref "R11") (pin "2") (pinfunction "2_2") (pintype "passive"))
    )
    (net (code "149") (name "Net-(IC1-P2[9]__USB_CONNECT__RXD2_(PAD19))") (class "Default")
      (node (ref "IC1") (pin "73") (pinfunction "P2[9]__USB_CONNECT__RXD2_(PAD19)_73") (pintype "bidirectional"))
      (node (ref "SW3") (pin "1") (pinfunction "1_1") (pintype "passive"))
    )
    (net (code "150") (name "Net-(IC1-P2[10]__EINT0__NMI)") (class "Default")
      (node (ref "IC1") (pin "51") (pinfunction "P2[10]__EINT0__NMI_51") (pintype "bidirectional"))
      (node (ref "SW2") (pin "1") (pinfunction "1_1") (pintype "passive"))
    )
    (net (code "151") (name "Net-(IC1-Reset_N)") (class "Default")
      (node (ref "IC1") (pin "4") (pinfunction "Reset_N_4") (pintype "passive"))
      (node (ref "SW1") (pin "1") (pinfunction "1_1") (pintype "passive"))
    )
    (net (code "152") (name "Net-(J4-Pad2)") (class "Default")
      (node (ref "J4") (pin "2") (pinfunction "2_2") (pintype "passive"))
      (node (ref "P7") (pin "10") (pinfunction "10_10") (pintype "passive"))
    )
    (net (code "153") (name "Net-(J5-Pad2)") (class "Default")
      (node (ref "J5") (pin "2") (pinfunction "2_2") (pintype "passive"))
      (node (ref "P9") (pin "10") (pinfunction "10_10") (pintype "passive"))
    )
    (net (code "154") (name "Net-(J18-Pad1)") (class "Default")
      (node (ref "J18") (pin "1") (pinfunction "1_1") (pintype "passive"))
      (node (ref "P1b") (pin "1") (pinfunction "1_1") (pintype "passive"))
    )
    (net (code "155") (name "Net-(P17-Common)") (class "Default")
      (node (ref "J16") (pin "1") (pinfunction "1_1") (pintype "passive"))
      (node (ref "P17") (pin "2") (pinfunction "Common_2") (pintype "passive"))
    )
    (net (code "156") (name "Net-(P17-Shield)") (class "Default")
      (node (ref "J17") (pin "1") (pinfunction "1_1") (pintype "passive"))
      (node (ref "P17") (pin "14") (pinfunction "Shield_14") (pintype "passive"))
    )
    (net (code "157") (name "Net-(Q1-B)") (class "Default")
      (node (ref "Q1") (pin "2") (pinfunction "B_2") (pintype "passive"))
      (node (ref "R16") (pin "2") (pinfunction "2_2") (pintype "passive"))
    )
    (net (code "158") (name "Net-(R16-Pad1)") (class "Default")
      (node (ref "R16") (pin "1") (pinfunction "1_1") (pintype "passive"))
      (node (ref "R17") (pin "W") (pinfunction "W_W") (pintype "passive"))
    )
    (net (code "159") (name "Net-(U1-VCC)") (class "Default")
      (node (ref "C3") (pin "2") (pinfunction "2_2") (pintype "passive"))
      (node (ref "C4") (pin "2") (pinfunction "2_2") (pintype "passive"))
      (node (ref "J1") (pin "2") (pinfunction "2_2") (pintype "passive"))
      (node (ref "P3") (pin "10") (pinfunction "10_10") (pintype "passive"))
      (node (ref "P5") (pin "10") (pinfunction "10_10") (pintype "passive"))
      (node (ref "U1") (pin "20") (pinfunction "VCC_20") (pintype "power_in"))
    )
    (net (code "160") (name "Net-(VR1-Vin)") (class "Default")
      (node (ref "C11") (pin "2") (pinfunction "2_2") (pintype "passive"))
      (node (ref "J6") (pin "2") (pinfunction "2_2") (pintype "passive"))
      (node (ref "VR1") (pin "3") (pinfunction "Vin_3") (pintype "power_in"))
    )
    (net (code "161") (name "Net-(VR2-Vin)") (class "Default")
      (node (ref "C17") (pin "2") (pinfunction "2_2") (pintype "passive"))
      (node (ref "J8") (pin "2") (pinfunction "2_2") (pintype "passive"))
      (node (ref "VR2") (pin "3") (pinfunction "Vin_3") (pintype "power_in"))
    )
    (net (code "162") (name "V_LCD") (class "Default")
      (node (ref "C21") (pin "2") (pinfunction "2_2") (pintype "passive"))
      (node (ref "C22") (pin "2") (pinfunction "2_2") (pintype "passive"))
      (node (ref "J11") (pin "2") (pinfunction "2_2") (pintype "passive"))
      (node (ref "P14") (pin "16") (pinfunction "16_16") (pintype "passive"))
      (node (ref "P16") (pin "16") (pinfunction "16_16") (pintype "passive"))
      (node (ref "R15") (pin "CW") (pinfunction "+_CW") (pintype "passive"))
      (node (ref "R19") (pin "1") (pinfunction "1_1") (pintype "passive"))
      (node (ref "R20") (pin "1") (pinfunction "1_1") (pintype "passive"))
      (node (ref "R21") (pin "1") (pinfunction "1_1") (pintype "passive"))
      (node (ref "R22") (pin "1") (pinfunction "1_1") (pintype "passive"))
      (node (ref "U2") (pin "10") (pinfunction "~{SRCLR}_10") (pintype "input"))
      (node (ref "U2") (pin "16") (pinfunction "VCC_16") (pintype "power_in"))
    )
    (net (code "163") (name "unconnected-(IC1-EXT_POW_(J4.14)-Pad80)") (class "Default")
      (node (ref "IC1") (pin "80") (pinfunction "EXT_POW_(J4.14)_80") (pintype "passive"))
    )
    (net (code "164") (name "unconnected-(IC1-V_IN-Pad2)") (class "Default")
      (node (ref "IC1") (pin "2") (pinfunction "V_IN_2") (pintype "power_in"))
    )
    (net (code "165") (name "unconnected-(IC1-V_bat-Pad3)") (class "Default")
      (node (ref "IC1") (pin "3") (pinfunction "V_bat_3") (pintype "passive"))
    )
    (net (code "166") (name "unconnected-(IC1-n.c.-Pad29)") (class "Default")
      (node (ref "IC1") (pin "29") (pinfunction "n.c._29") (pintype "passive"))
    )
    (net (code "167") (name "unconnected-(IC1-n.c.-Pad30)") (class "Default")
      (node (ref "IC1") (pin "30") (pinfunction "n.c._30") (pintype "passive"))
    )
    (net (code "168") (name "unconnected-(IC1-n.c.-Pad31)") (class "Default")
      (node (ref "IC1") (pin "31") (pinfunction "n.c._31") (pintype "passive"))
    )
    (net (code "169") (name "unconnected-(P2-Pad10)") (class "Default")
      (node (ref "P2") (pin "10") (pinfunction "10_10") (pintype "passive"))
    )
    (net (code "170") (name "unconnected-(P4-VBus-Pad1)") (class "Default")
      (node (ref "P4") (pin "1") (pinfunction "VBus_1") (pintype "passive"))
    )
    (net (code "171") (name "unconnected-(P7-Pad6)") (class "Default")
      (node (ref "P7") (pin "6") (pinfunction "6_6") (pintype "passive"))
    )
    (net (code "172") (name "unconnected-(P7-Pad7)") (class "Default")
      (node (ref "P7") (pin "7") (pinfunction "7_7") (pintype "passive"))
    )
    (net (code "173") (name "unconnected-(P7-Pad8)") (class "Default")
      (node (ref "P7") (pin "8") (pinfunction "8_8") (pintype "passive"))
    )
    (net (code "174") (name "unconnected-(P9-Pad8)") (class "Default")
      (node (ref "P9") (pin "8") (pinfunction "8_8") (pintype "passive"))
    )
    (net (code "175") (name "unconnected-(P10-Pad3)") (class "Default")
      (node (ref "P10") (pin "3") (pinfunction "3_3") (pintype "passive"))
    )
    (net (code "176") (name "unconnected-(P17-Led_Grn_A-Pad13)") (class "Default")
      (node (ref "P17") (pin "13") (pinfunction "Led_Grn_A_13") (pintype "passive"))
    )
    (net (code "177") (name "unconnected-(P17-Led_Grn_K-Pad12)") (class "Default")
      (node (ref "P17") (pin "12") (pinfunction "Led_Grn_K_12") (pintype "passive"))
    )
    (net (code "178") (name "unconnected-(P17-Led_Yel_A-Pad7)") (class "Default")
      (node (ref "P17") (pin "7") (pinfunction "Led_Yel_A_7") (pintype "passive"))
    )
    (net (code "179") (name "unconnected-(P17-Led_Yel_K-Pad6)") (class "Default")
      (node (ref "P17") (pin "6") (pinfunction "Led_Yel_K_6") (pintype "passive"))
    )
    (net (code "180") (name "unconnected-(P17-VC+-Pad8)") (class "Default")
      (node (ref "P17") (pin "8") (pinfunction "VC+_8") (pintype "passive"))
    )
    (net (code "181") (name "unconnected-(P17-VC+-Pad10)") (class "Default")
      (node (ref "P17") (pin "10") (pinfunction "VC+_10") (pintype "passive"))
    )
    (net (code "182") (name "unconnected-(P17-VC--Pad9)") (class "Default")
      (node (ref "P17") (pin "9") (pinfunction "VC-_9") (pintype "passive"))
    )
    (net (code "183") (name "unconnected-(P17-VC--Pad11)") (class "Default")
      (node (ref "P17") (pin "11") (pinfunction "VC-_11") (pintype "passive"))
    )
    (net (code "184") (name "unconnected-(SW1-Pad2)") (class "Default")
      (node (ref "SW1") (pin "2") (pinfunction "2_2") (pintype "passive"))
    )
    (net (code "185") (name "unconnected-(SW2-Pad2)") (class "Default")
      (node (ref "SW2") (pin "2") (pinfunction "2_2") (pintype "passive"))
    )
    (net (code "186") (name "unconnected-(SW3-Pad2)") (class "Default")
      (node (ref "SW3") (pin "2") (pinfunction "2_2") (pintype "passive"))
    )
    (net (code "187") (name "unconnected-(U2-QH'-Pad9)") (class "Default")
      (node (ref "U2") (pin "9") (pinfunction "QH'_9") (pintype "output"))
    )
  )
)
